# ebox.net
KiCad netlist of a schematic drawn in EAGLE
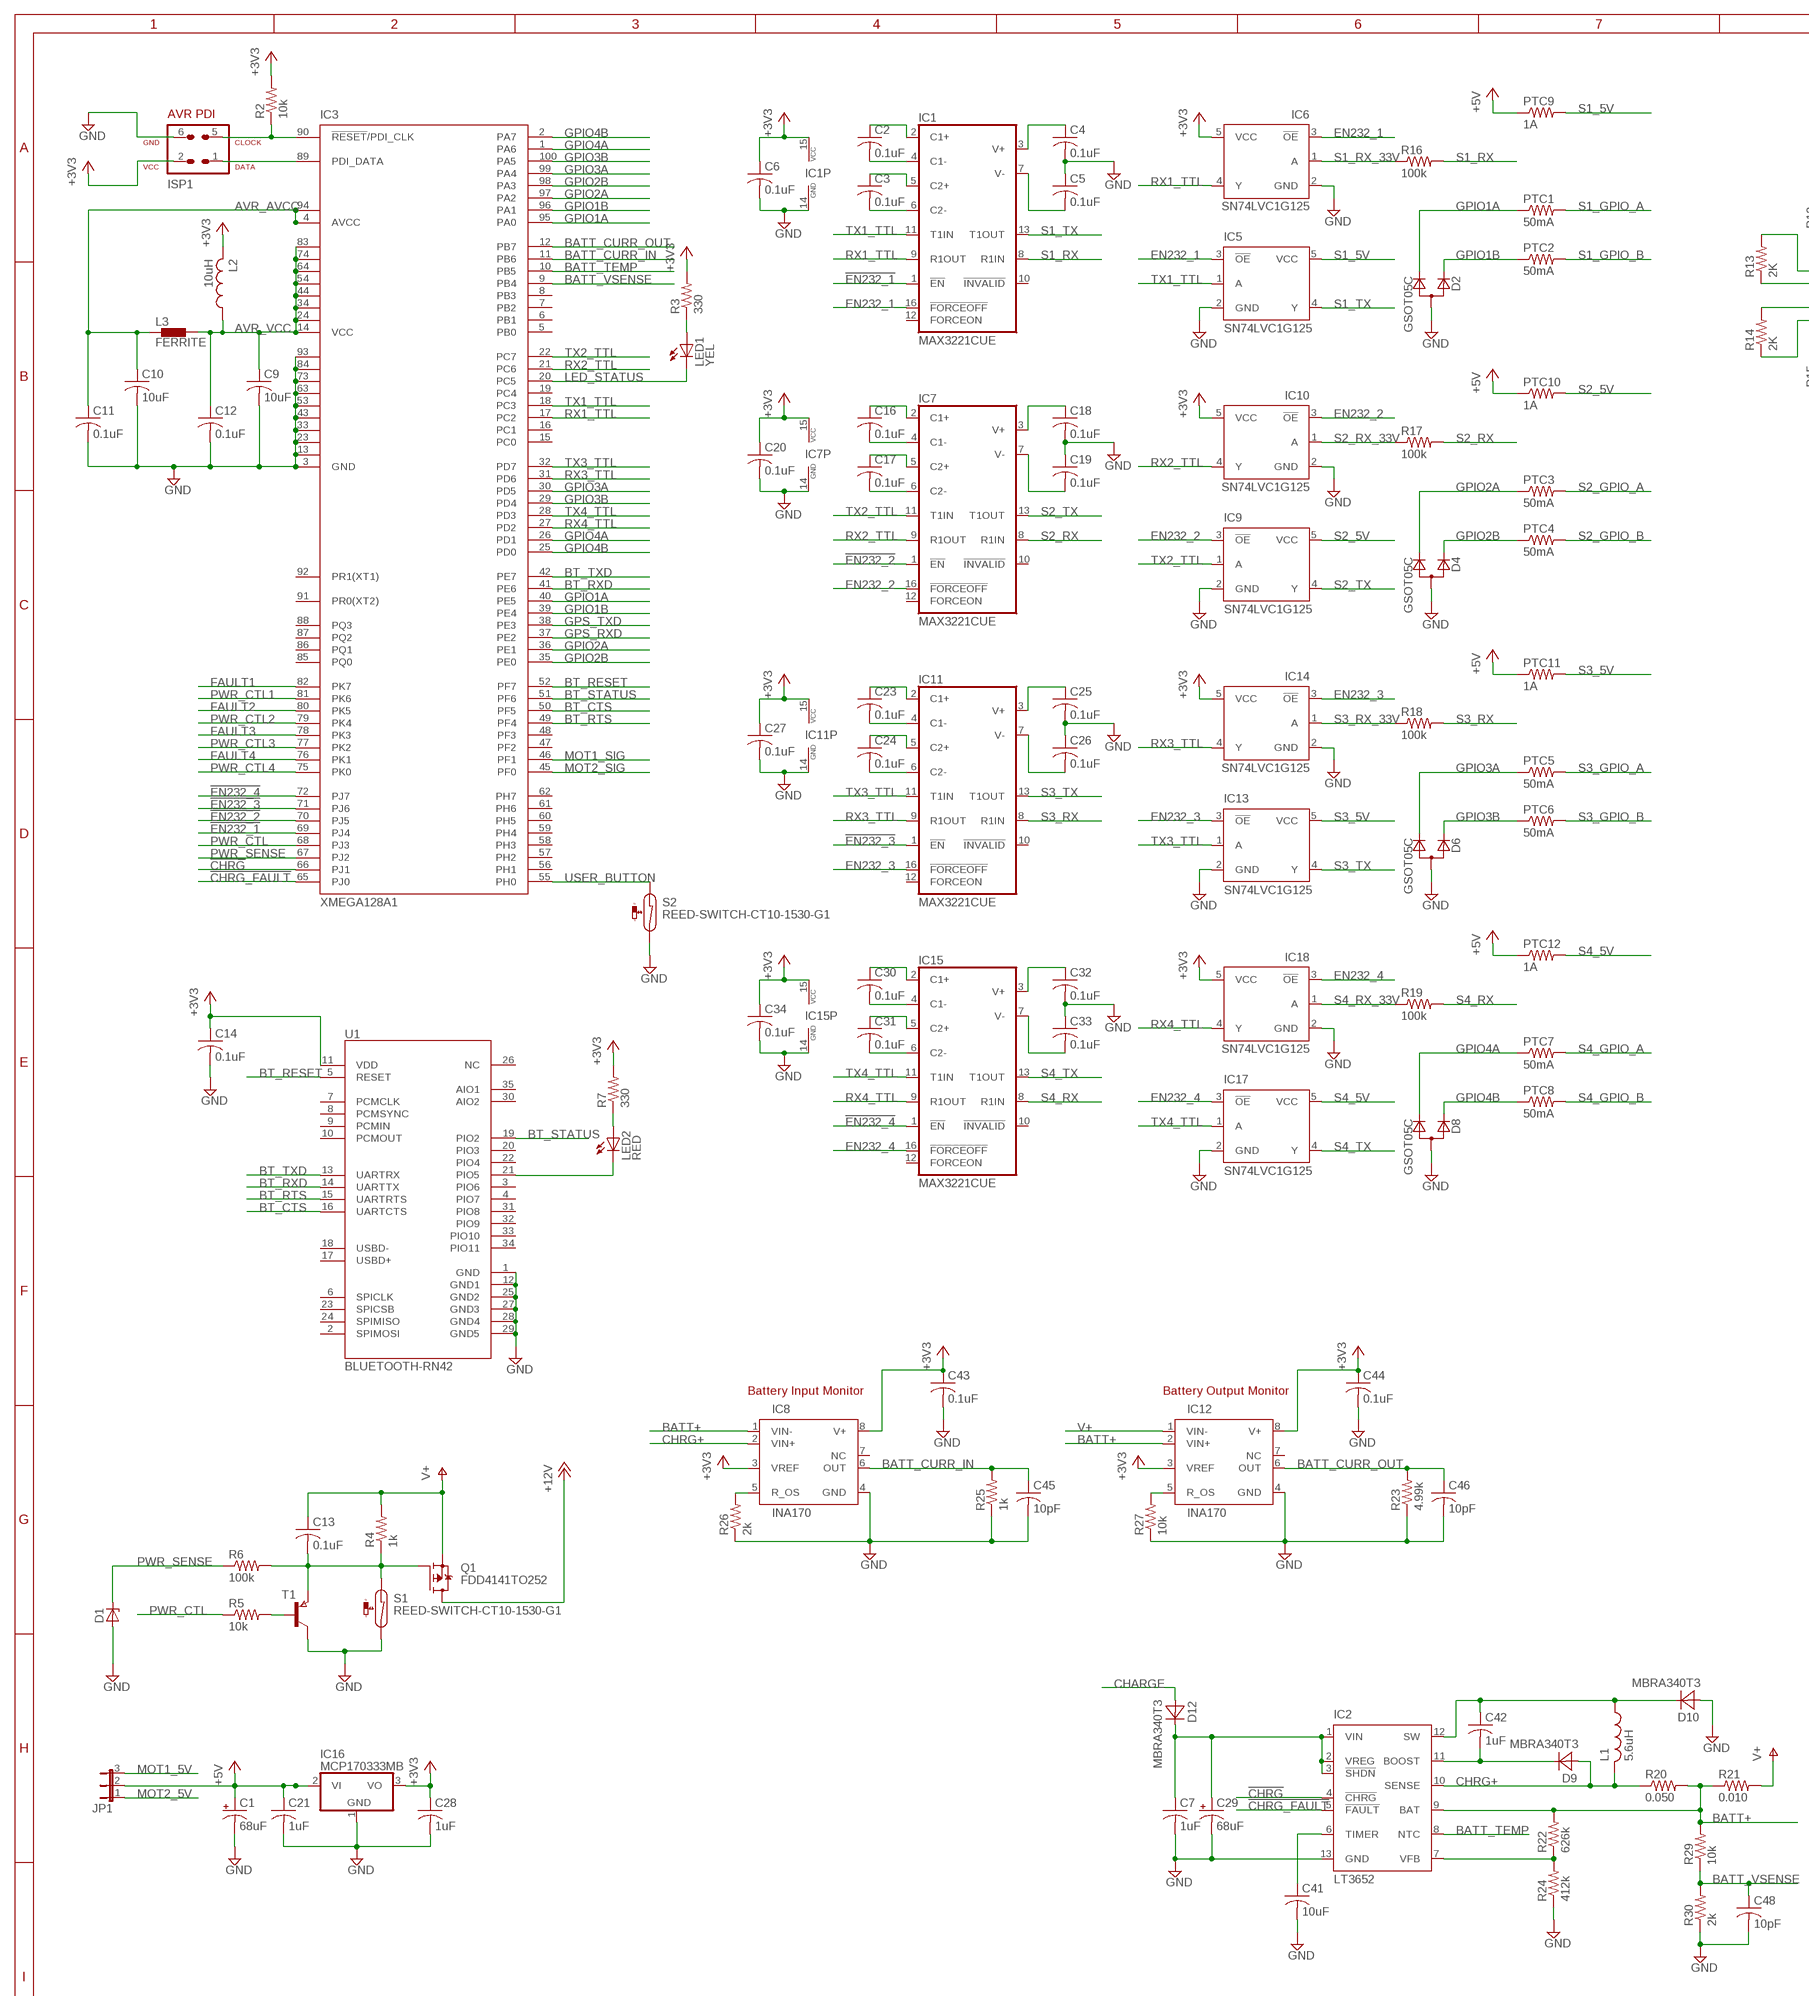
[diagram p0: schematic, sheet 1, part 1 of 2]
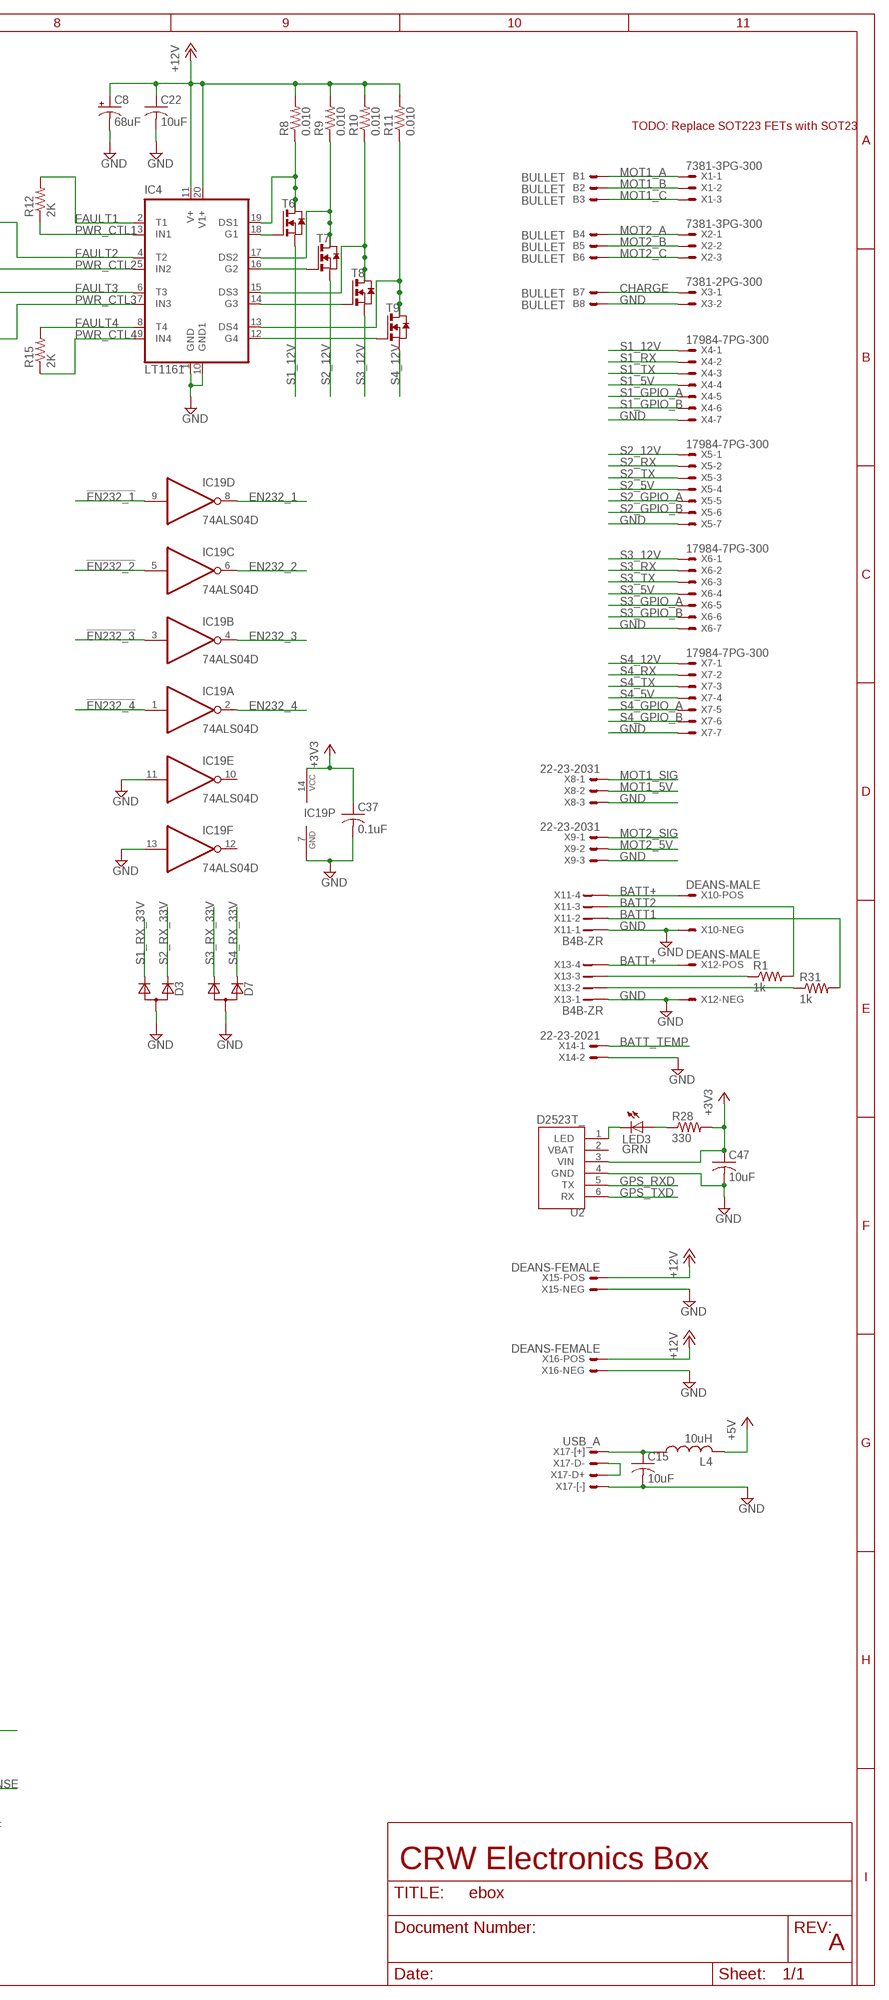
[diagram p1: schematic, sheet 1, part 2 of 2]

(export (version "E")
  (design (tool "Eeschema 10.0.6"))
  (components
    (comp (ref "B1")
      (value "BULLET")
      (footprint "eagle-import:BULLET")
      (libsource (lib "eagle-import") (part "BULLET"))
    )
    (comp (ref "B2")
      (value "BULLET")
      (footprint "eagle-import:BULLET")
      (libsource (lib "eagle-import") (part "BULLET"))
    )
    (comp (ref "B3")
      (value "BULLET")
      (footprint "eagle-import:BULLET")
      (libsource (lib "eagle-import") (part "BULLET"))
    )
    (comp (ref "B4")
      (value "BULLET")
      (footprint "eagle-import:BULLET")
      (libsource (lib "eagle-import") (part "BULLET"))
    )
    (comp (ref "B5")
      (value "BULLET")
      (footprint "eagle-import:BULLET")
      (libsource (lib "eagle-import") (part "BULLET"))
    )
    (comp (ref "B6")
      (value "BULLET")
      (footprint "eagle-import:BULLET")
      (libsource (lib "eagle-import") (part "BULLET"))
    )
    (comp (ref "B7")
      (value "BULLET")
      (footprint "eagle-import:BULLET")
      (libsource (lib "eagle-import") (part "BULLET"))
    )
    (comp (ref "B8")
      (value "BULLET")
      (footprint "eagle-import:BULLET")
      (libsource (lib "eagle-import") (part "BULLET"))
    )
    (comp (ref "C1")
      (value "68uF")
      (footprint "eagle-import:PANASONIC_D")
      (libsource (lib "eagle-import") (part "CPOL-USD"))
    )
    (comp (ref "C2")
      (value "0.1uF")
      (footprint "eagle-import:C0805")
      (libsource (lib "eagle-import") (part "C-USC0805"))
    )
    (comp (ref "C3")
      (value "0.1uF")
      (footprint "eagle-import:C0805")
      (libsource (lib "eagle-import") (part "C-USC0805"))
    )
    (comp (ref "C4")
      (value "0.1uF")
      (footprint "eagle-import:C0805")
      (libsource (lib "eagle-import") (part "C-USC0805"))
    )
    (comp (ref "C5")
      (value "0.1uF")
      (footprint "eagle-import:C0805")
      (libsource (lib "eagle-import") (part "C-USC0805"))
    )
    (comp (ref "C6")
      (value "0.1uF")
      (footprint "eagle-import:C0805")
      (libsource (lib "eagle-import") (part "C-USC0805"))
    )
    (comp (ref "C7")
      (value "1uF")
      (footprint "eagle-import:C0805")
      (libsource (lib "eagle-import") (part "C-USC0805"))
    )
    (comp (ref "C8")
      (value "68uF")
      (footprint "eagle-import:PANASONIC_D")
      (libsource (lib "eagle-import") (part "CPOL-USD"))
    )
    (comp (ref "C9")
      (value "10uF")
      (footprint "eagle-import:C0805")
      (libsource (lib "eagle-import") (part "C-USC0805"))
    )
    (comp (ref "C10")
      (value "10uF")
      (footprint "eagle-import:C0805")
      (libsource (lib "eagle-import") (part "C-USC0805"))
    )
    (comp (ref "C11")
      (value "0.1uF")
      (footprint "eagle-import:C0805")
      (libsource (lib "eagle-import") (part "C-USC0805"))
    )
    (comp (ref "C12")
      (value "0.1uF")
      (footprint "eagle-import:C0805")
      (libsource (lib "eagle-import") (part "C-USC0805"))
    )
    (comp (ref "C13")
      (value "0.1uF")
      (footprint "eagle-import:C0805")
      (libsource (lib "eagle-import") (part "C-USC0805"))
    )
    (comp (ref "C14")
      (value "0.1uF")
      (footprint "eagle-import:C0805")
      (libsource (lib "eagle-import") (part "C-USC0805"))
    )
    (comp (ref "C15")
      (value "10uF")
      (footprint "eagle-import:C0805")
      (libsource (lib "eagle-import") (part "C-USC0805"))
    )
    (comp (ref "C16")
      (value "0.1uF")
      (footprint "eagle-import:C0805")
      (libsource (lib "eagle-import") (part "C-USC0805"))
    )
    (comp (ref "C17")
      (value "0.1uF")
      (footprint "eagle-import:C0805")
      (libsource (lib "eagle-import") (part "C-USC0805"))
    )
    (comp (ref "C18")
      (value "0.1uF")
      (footprint "eagle-import:C0805")
      (libsource (lib "eagle-import") (part "C-USC0805"))
    )
    (comp (ref "C19")
      (value "0.1uF")
      (footprint "eagle-import:C0805")
      (libsource (lib "eagle-import") (part "C-USC0805"))
    )
    (comp (ref "C20")
      (value "0.1uF")
      (footprint "eagle-import:C0805")
      (libsource (lib "eagle-import") (part "C-USC0805"))
    )
    (comp (ref "C21")
      (value "1uF")
      (footprint "eagle-import:C0805")
      (libsource (lib "eagle-import") (part "C-USC0805"))
    )
    (comp (ref "C22")
      (value "10uF")
      (footprint "eagle-import:C0805")
      (libsource (lib "eagle-import") (part "C-USC0805"))
    )
    (comp (ref "C23")
      (value "0.1uF")
      (footprint "eagle-import:C0805")
      (libsource (lib "eagle-import") (part "C-USC0805"))
    )
    (comp (ref "C24")
      (value "0.1uF")
      (footprint "eagle-import:C0805")
      (libsource (lib "eagle-import") (part "C-USC0805"))
    )
    (comp (ref "C25")
      (value "0.1uF")
      (footprint "eagle-import:C0805")
      (libsource (lib "eagle-import") (part "C-USC0805"))
    )
    (comp (ref "C26")
      (value "0.1uF")
      (footprint "eagle-import:C0805")
      (libsource (lib "eagle-import") (part "C-USC0805"))
    )
    (comp (ref "C27")
      (value "0.1uF")
      (footprint "eagle-import:C0805")
      (libsource (lib "eagle-import") (part "C-USC0805"))
    )
    (comp (ref "C28")
      (value "1uF")
      (footprint "eagle-import:C0805")
      (libsource (lib "eagle-import") (part "C-USC0805"))
    )
    (comp (ref "C29")
      (value "68uF")
      (footprint "eagle-import:PANASONIC_D")
      (libsource (lib "eagle-import") (part "CPOL-USD"))
    )
    (comp (ref "C30")
      (value "0.1uF")
      (footprint "eagle-import:C0805")
      (libsource (lib "eagle-import") (part "C-USC0805"))
    )
    (comp (ref "C31")
      (value "0.1uF")
      (footprint "eagle-import:C0805")
      (libsource (lib "eagle-import") (part "C-USC0805"))
    )
    (comp (ref "C32")
      (value "0.1uF")
      (footprint "eagle-import:C0805")
      (libsource (lib "eagle-import") (part "C-USC0805"))
    )
    (comp (ref "C33")
      (value "0.1uF")
      (footprint "eagle-import:C0805")
      (libsource (lib "eagle-import") (part "C-USC0805"))
    )
    (comp (ref "C34")
      (value "0.1uF")
      (footprint "eagle-import:C0805")
      (libsource (lib "eagle-import") (part "C-USC0805"))
    )
    (comp (ref "C37")
      (value "0.1uF")
      (footprint "eagle-import:C0805")
      (libsource (lib "eagle-import") (part "C-USC0805"))
    )
    (comp (ref "C41")
      (value "10uF")
      (footprint "eagle-import:C0805")
      (libsource (lib "eagle-import") (part "C-USC0805"))
    )
    (comp (ref "C42")
      (value "1uF")
      (footprint "eagle-import:C0805")
      (libsource (lib "eagle-import") (part "C-USC0805"))
    )
    (comp (ref "C43")
      (value "0.1uF")
      (footprint "eagle-import:C0805")
      (libsource (lib "eagle-import") (part "C-USC0805"))
    )
    (comp (ref "C44")
      (value "0.1uF")
      (footprint "eagle-import:C0805")
      (libsource (lib "eagle-import") (part "C-USC0805"))
    )
    (comp (ref "C45")
      (value "10pF")
      (footprint "eagle-import:C0805")
      (libsource (lib "eagle-import") (part "C-USC0805"))
    )
    (comp (ref "C46")
      (value "10pF")
      (footprint "eagle-import:C0805")
      (libsource (lib "eagle-import") (part "C-USC0805"))
    )
    (comp (ref "C47")
      (value "10uF")
      (footprint "eagle-import:C0805")
      (libsource (lib "eagle-import") (part "C-USC0805"))
    )
    (comp (ref "C48")
      (value "10pF")
      (footprint "eagle-import:C0805")
      (libsource (lib "eagle-import") (part "C-USC0805"))
    )
    (comp (ref "D1")
      (value "ZENER-DIODESOT23")
      (footprint "eagle-import:SOT23")
      (libsource (lib "eagle-import") (part "ZENER-DIODESOT23"))
    )
    (comp (ref "D2")
      (value "GSOT05C")
      (footprint "eagle-import:SOT-23")
      (libsource (lib "eagle-import") (part "D_2CSOT23"))
    )
    (comp (ref "D3")
      (value "D_2CSOT23")
      (footprint "eagle-import:SOT-23")
      (libsource (lib "eagle-import") (part "D_2CSOT23"))
    )
    (comp (ref "D4")
      (value "GSOT05C")
      (footprint "eagle-import:SOT-23")
      (libsource (lib "eagle-import") (part "D_2CSOT23"))
    )
    (comp (ref "D6")
      (value "GSOT05C")
      (footprint "eagle-import:SOT-23")
      (libsource (lib "eagle-import") (part "D_2CSOT23"))
    )
    (comp (ref "D7")
      (value "D_2CSOT23")
      (footprint "eagle-import:SOT-23")
      (libsource (lib "eagle-import") (part "D_2CSOT23"))
    )
    (comp (ref "D8")
      (value "GSOT05C")
      (footprint "eagle-import:SOT-23")
      (libsource (lib "eagle-import") (part "D_2CSOT23"))
    )
    (comp (ref "D9")
      (value "MBRA340T3")
      (footprint "eagle-import:SMA")
      (libsource (lib "eagle-import") (part "MBRA340T3"))
    )
    (comp (ref "D10")
      (value "MBRA340T3")
      (footprint "eagle-import:SMA")
      (libsource (lib "eagle-import") (part "MBRA340T3"))
    )
    (comp (ref "D12")
      (value "MBRA340T3")
      (footprint "eagle-import:SMA")
      (libsource (lib "eagle-import") (part "MBRA340T3"))
    )
    (comp (ref "IC1")
      (value "MAX3221CUE")
      (footprint "eagle-import:TSSOP16")
      (fields (field (name "MF") "MAXIM") (field (name "MPN") "MAX3221CUE+"))
      (libsource (lib "eagle-import") (part "MAX3221UEC"))
    )
    (comp (ref "IC2")
      (value "LT3652")
      (footprint "eagle-import:MSOP12-MSE")
      (fields (field (name "MPN") "AD7992BRMZ-0"))
      (libsource (lib "eagle-import") (part "LT3652"))
    )
    (comp (ref "IC3")
      (value "XMEGA128A1")
      (footprint "eagle-import:TQFP100")
      (libsource (lib "eagle-import") (part "XMEGA128A1"))
    )
    (comp (ref "IC4")
      (value "LT1161")
      (footprint "eagle-import:SOIC20R")
      (libsource (lib "eagle-import") (part "LT1161"))
    )
    (comp (ref "IC5")
      (value "SN74LVC1G125")
      (footprint "eagle-import:SOT23-DBV")
      (libsource (lib "eagle-import") (part "SN74LVC1G125"))
    )
    (comp (ref "IC6")
      (value "SN74LVC1G125")
      (footprint "eagle-import:SOT23-DBV")
      (libsource (lib "eagle-import") (part "SN74LVC1G125"))
    )
    (comp (ref "IC7")
      (value "MAX3221CUE")
      (footprint "eagle-import:TSSOP16")
      (fields (field (name "MF") "MAXIM") (field (name "MPN") "MAX3221CUE+"))
      (libsource (lib "eagle-import") (part "MAX3221UEC"))
    )
    (comp (ref "IC8")
      (value "INA170")
      (footprint "eagle-import:MSOP8")
      (libsource (lib "eagle-import") (part "INA170"))
    )
    (comp (ref "IC9")
      (value "SN74LVC1G125")
      (footprint "eagle-import:SOT23-DBV")
      (libsource (lib "eagle-import") (part "SN74LVC1G125"))
    )
    (comp (ref "IC10")
      (value "SN74LVC1G125")
      (footprint "eagle-import:SOT23-DBV")
      (libsource (lib "eagle-import") (part "SN74LVC1G125"))
    )
    (comp (ref "IC11")
      (value "MAX3221CUE")
      (footprint "eagle-import:TSSOP16")
      (fields (field (name "MF") "MAXIM") (field (name "MPN") "MAX3221CUE+"))
      (libsource (lib "eagle-import") (part "MAX3221UEC"))
    )
    (comp (ref "IC12")
      (value "INA170")
      (footprint "eagle-import:MSOP8")
      (libsource (lib "eagle-import") (part "INA170"))
    )
    (comp (ref "IC13")
      (value "SN74LVC1G125")
      (footprint "eagle-import:SOT23-DBV")
      (libsource (lib "eagle-import") (part "SN74LVC1G125"))
    )
    (comp (ref "IC14")
      (value "SN74LVC1G125")
      (footprint "eagle-import:SOT23-DBV")
      (libsource (lib "eagle-import") (part "SN74LVC1G125"))
    )
    (comp (ref "IC15")
      (value "MAX3221CUE")
      (footprint "eagle-import:TSSOP16")
      (fields (field (name "MF") "MAXIM") (field (name "MPN") "MAX3221CUE+"))
      (libsource (lib "eagle-import") (part "MAX3221UEC"))
    )
    (comp (ref "IC16")
      (value "MCP170333MB")
      (footprint "eagle-import:SOT89")
      (libsource (lib "eagle-import") (part "MCP1703MB33"))
    )
    (comp (ref "IC17")
      (value "SN74LVC1G125")
      (footprint "eagle-import:SOT23-DBV")
      (libsource (lib "eagle-import") (part "SN74LVC1G125"))
    )
    (comp (ref "IC18")
      (value "SN74LVC1G125")
      (footprint "eagle-import:SOT23-DBV")
      (libsource (lib "eagle-import") (part "SN74LVC1G125"))
    )
    (comp (ref "IC19")
      (value "74ALS04D")
      (footprint "eagle-import:SO14")
      (libsource (lib "eagle-import") (part "7404DALS"))
    )
    (comp (ref "ISP1")
      (value "AVR-PDIVERT")
      (footprint "eagle-import:AVR-ISP-6")
      (libsource (lib "eagle-import") (part "AVR-PDIVERT"))
    )
    (comp (ref "JP1")
      (value "JP2E")
      (footprint "eagle-import:JP2")
      (libsource (lib "eagle-import") (part "JP2E"))
    )
    (comp (ref "L1")
      (value "5.6uH")
      (footprint "eagle-import:IHLP-2020CZ-11")
      (libsource (lib "eagle-import") (part "IHLP-2020CZ-11"))
    )
    (comp (ref "L2")
      (value "10uH")
      (footprint "eagle-import:L2012C")
      (libsource (lib "eagle-import") (part "L-USL2012C"))
    )
    (comp (ref "L3")
      (value "FERRITE")
      (footprint "eagle-import:0402")
      (libsource (lib "eagle-import") (part "BML15HB121SN1"))
    )
    (comp (ref "L4")
      (value "10uH")
      (footprint "eagle-import:L2012C")
      (libsource (lib "eagle-import") (part "L-USL2012C"))
    )
    (comp (ref "LED1")
      (value "YEL")
      (footprint "eagle-import:CHIPLED_1206")
      (libsource (lib "eagle-import") (part "LEDCHIPLED_1206"))
    )
    (comp (ref "LED2")
      (value "RED")
      (footprint "eagle-import:CHIPLED_1206")
      (libsource (lib "eagle-import") (part "LEDCHIPLED_1206"))
    )
    (comp (ref "LED3")
      (value "GRN")
      (footprint "eagle-import:CHIPLED_1206")
      (libsource (lib "eagle-import") (part "LEDCHIPLED_1206"))
    )
    (comp (ref "PTC1")
      (value "50mA")
      (footprint "eagle-import:R1206")
      (libsource (lib "eagle-import") (part "R-US_R1206"))
    )
    (comp (ref "PTC2")
      (value "50mA")
      (footprint "eagle-import:R1206")
      (libsource (lib "eagle-import") (part "R-US_R1206"))
    )
    (comp (ref "PTC3")
      (value "50mA")
      (footprint "eagle-import:R1206")
      (libsource (lib "eagle-import") (part "R-US_R1206"))
    )
    (comp (ref "PTC4")
      (value "50mA")
      (footprint "eagle-import:R1206")
      (libsource (lib "eagle-import") (part "R-US_R1206"))
    )
    (comp (ref "PTC5")
      (value "50mA")
      (footprint "eagle-import:R1206")
      (libsource (lib "eagle-import") (part "R-US_R1206"))
    )
    (comp (ref "PTC6")
      (value "50mA")
      (footprint "eagle-import:R1206")
      (libsource (lib "eagle-import") (part "R-US_R1206"))
    )
    (comp (ref "PTC7")
      (value "50mA")
      (footprint "eagle-import:R1206")
      (libsource (lib "eagle-import") (part "R-US_R1206"))
    )
    (comp (ref "PTC8")
      (value "50mA")
      (footprint "eagle-import:R1206")
      (libsource (lib "eagle-import") (part "R-US_R1206"))
    )
    (comp (ref "PTC9")
      (value "1A")
      (footprint "eagle-import:R1206")
      (libsource (lib "eagle-import") (part "R-US_R1206"))
    )
    (comp (ref "PTC10")
      (value "1A")
      (footprint "eagle-import:R1206")
      (libsource (lib "eagle-import") (part "R-US_R1206"))
    )
    (comp (ref "PTC11")
      (value "1A")
      (footprint "eagle-import:R1206")
      (libsource (lib "eagle-import") (part "R-US_R1206"))
    )
    (comp (ref "PTC12")
      (value "1A")
      (footprint "eagle-import:R1206")
      (libsource (lib "eagle-import") (part "R-US_R1206"))
    )
    (comp (ref "Q1")
      (value "FDD4141TO252")
      (footprint "eagle-import:TO252")
      (libsource (lib "eagle-import") (part "FDD4141TO252"))
    )
    (comp (ref "R1")
      (value "1k")
      (footprint "eagle-import:R0805")
      (libsource (lib "eagle-import") (part "R-US_R0805"))
    )
    (comp (ref "R2")
      (value "10k")
      (footprint "eagle-import:R0805")
      (libsource (lib "eagle-import") (part "R-US_R0805"))
    )
    (comp (ref "R3")
      (value "330")
      (footprint "eagle-import:R0805")
      (libsource (lib "eagle-import") (part "R-US_R0805"))
    )
    (comp (ref "R4")
      (value "1k")
      (footprint "eagle-import:R0805")
      (libsource (lib "eagle-import") (part "R-US_R0805"))
    )
    (comp (ref "R5")
      (value "10k")
      (footprint "eagle-import:R0805")
      (libsource (lib "eagle-import") (part "R-US_R0805"))
    )
    (comp (ref "R6")
      (value "100k")
      (footprint "eagle-import:R0805")
      (libsource (lib "eagle-import") (part "R-US_R0805"))
    )
    (comp (ref "R7")
      (value "330")
      (footprint "eagle-import:R0805")
      (libsource (lib "eagle-import") (part "R-US_R0805"))
    )
    (comp (ref "R8")
      (value "0.010")
      (footprint "eagle-import:R6332")
      (libsource (lib "eagle-import") (part "R-US_R6332"))
    )
    (comp (ref "R9")
      (value "0.010")
      (footprint "eagle-import:R6332")
      (libsource (lib "eagle-import") (part "R-US_R6332"))
    )
    (comp (ref "R10")
      (value "0.010")
      (footprint "eagle-import:R6332")
      (libsource (lib "eagle-import") (part "R-US_R6332"))
    )
    (comp (ref "R11")
      (value "0.010")
      (footprint "eagle-import:R6332")
      (libsource (lib "eagle-import") (part "R-US_R6332"))
    )
    (comp (ref "R12")
      (value "2K")
      (footprint "eagle-import:R0805")
      (libsource (lib "eagle-import") (part "R-US_R0805"))
    )
    (comp (ref "R13")
      (value "2K")
      (footprint "eagle-import:R0805")
      (libsource (lib "eagle-import") (part "R-US_R0805"))
    )
    (comp (ref "R14")
      (value "2K")
      (footprint "eagle-import:R0805")
      (libsource (lib "eagle-import") (part "R-US_R0805"))
    )
    (comp (ref "R15")
      (value "2K")
      (footprint "eagle-import:R0805")
      (libsource (lib "eagle-import") (part "R-US_R0805"))
    )
    (comp (ref "R16")
      (value "100k")
      (footprint "eagle-import:R0805")
      (libsource (lib "eagle-import") (part "R-US_R0805"))
    )
    (comp (ref "R17")
      (value "100k")
      (footprint "eagle-import:R0805")
      (libsource (lib "eagle-import") (part "R-US_R0805"))
    )
    (comp (ref "R18")
      (value "100k")
      (footprint "eagle-import:R0805")
      (libsource (lib "eagle-import") (part "R-US_R0805"))
    )
    (comp (ref "R19")
      (value "100k")
      (footprint "eagle-import:R0805")
      (libsource (lib "eagle-import") (part "R-US_R0805"))
    )
    (comp (ref "R20")
      (value "0.050")
      (footprint "eagle-import:R6332")
      (libsource (lib "eagle-import") (part "R-US_R6332"))
    )
    (comp (ref "R21")
      (value "0.010")
      (footprint "eagle-import:R6332")
      (libsource (lib "eagle-import") (part "R-US_R6332"))
    )
    (comp (ref "R22")
      (value "626k")
      (footprint "eagle-import:R0805")
      (libsource (lib "eagle-import") (part "R-US_R0805"))
    )
    (comp (ref "R23")
      (value "4.99k")
      (footprint "eagle-import:R0805")
      (libsource (lib "eagle-import") (part "R-US_R0805"))
    )
    (comp (ref "R24")
      (value "412k")
      (footprint "eagle-import:R0805")
      (libsource (lib "eagle-import") (part "R-US_R0805"))
    )
    (comp (ref "R25")
      (value "1k")
      (footprint "eagle-import:R0805")
      (libsource (lib "eagle-import") (part "R-US_R0805"))
    )
    (comp (ref "R26")
      (value "2k")
      (footprint "eagle-import:R0805")
      (libsource (lib "eagle-import") (part "R-US_R0805"))
    )
    (comp (ref "R27")
      (value "10k")
      (footprint "eagle-import:R0805")
      (libsource (lib "eagle-import") (part "R-US_R0805"))
    )
    (comp (ref "R28")
      (value "330")
      (footprint "eagle-import:R0805")
      (libsource (lib "eagle-import") (part "R-US_R0805"))
    )
    (comp (ref "R29")
      (value "10k")
      (footprint "eagle-import:R0805")
      (libsource (lib "eagle-import") (part "R-US_R0805"))
    )
    (comp (ref "R30")
      (value "2k")
      (footprint "eagle-import:R0805")
      (libsource (lib "eagle-import") (part "R-US_R0805"))
    )
    (comp (ref "R31")
      (value "1k")
      (footprint "eagle-import:R0805")
      (libsource (lib "eagle-import") (part "R-US_R0805"))
    )
    (comp (ref "S1")
      (value "REED-SWITCH-CT10-1530-G1")
      (footprint "eagle-import:CT10-G1")
      (fields (field (name "MF") "COTO TECHNOLOGY") (field (name "MPN") "CT10-1530-G1"))
      (libsource (lib "eagle-import") (part "REED-SWITCH-CT10-1530-G1"))
    )
    (comp (ref "S2")
      (value "REED-SWITCH-CT10-1530-G1")
      (footprint "eagle-import:CT10-G1")
      (fields (field (name "MF") "COTO TECHNOLOGY") (field (name "MPN") "CT10-1530-G1"))
      (libsource (lib "eagle-import") (part "REED-SWITCH-CT10-1530-G1"))
    )
    (comp (ref "T1")
      (value "PNPSOT23")
      (footprint "eagle-import:SOT-23")
      (fields (field (name "MPN") "DSS20200L-7"))
      (libsource (lib "eagle-import") (part "PNPSOT23"))
    )
    (comp (ref "T6")
      (value "NMOSSOT23-6")
      (footprint "eagle-import:SOT23-6")
      (libsource (lib "eagle-import") (part "NMOSSOT23-6"))
    )
    (comp (ref "T7")
      (value "NMOSSOT23-6")
      (footprint "eagle-import:SOT23-6")
      (libsource (lib "eagle-import") (part "NMOSSOT23-6"))
    )
    (comp (ref "T8")
      (value "NMOSSOT23-6")
      (footprint "eagle-import:SOT23-6")
      (libsource (lib "eagle-import") (part "NMOSSOT23-6"))
    )
    (comp (ref "T9")
      (value "NMOSSOT23-6")
      (footprint "eagle-import:SOT23-6")
      (libsource (lib "eagle-import") (part "NMOSSOT23-6"))
    )
    (comp (ref "U1")
      (value "BLUETOOTH-RN42")
      (footprint "eagle-import:RN41")
      (libsource (lib "eagle-import") (part "BLUETOOTH-RN41{dblquote}"))
    )
    (comp (ref "U2")
      (value "D2523T_")
      (footprint "eagle-import:EM406")
      (libsource (lib "eagle-import") (part "D2523T_"))
    )
    (comp (ref "X1")
      (value "7381-3PG-300")
      (footprint "eagle-import:7381-3PG-300")
      (libsource (lib "eagle-import") (part "7381-3PG-300"))
    )
    (comp (ref "X2")
      (value "7381-3PG-300")
      (footprint "eagle-import:7381-3PG-300")
      (libsource (lib "eagle-import") (part "7381-3PG-300"))
    )
    (comp (ref "X3")
      (value "7381-2PG-300")
      (footprint "eagle-import:7381-2PG-300")
      (libsource (lib "eagle-import") (part "7381-2PG-300"))
    )
    (comp (ref "X4")
      (value "17984-7PG-300")
      (footprint "eagle-import:17984-7PG-300")
      (libsource (lib "eagle-import") (part "17984-7PG-300"))
    )
    (comp (ref "X5")
      (value "17984-7PG-300")
      (footprint "eagle-import:17984-7PG-300")
      (libsource (lib "eagle-import") (part "17984-7PG-300"))
    )
    (comp (ref "X6")
      (value "17984-7PG-300")
      (footprint "eagle-import:17984-7PG-300")
      (libsource (lib "eagle-import") (part "17984-7PG-300"))
    )
    (comp (ref "X7")
      (value "17984-7PG-300")
      (footprint "eagle-import:17984-7PG-300")
      (libsource (lib "eagle-import") (part "17984-7PG-300"))
    )
    (comp (ref "X8")
      (value "22-23-2031")
      (footprint "eagle-import:22-23-2031")
      (fields (field (name "MF") "MOLEX"))
      (libsource (lib "eagle-import") (part "22-23-2031"))
    )
    (comp (ref "X9")
      (value "22-23-2031")
      (footprint "eagle-import:22-23-2031")
      (fields (field (name "MF") "MOLEX"))
      (libsource (lib "eagle-import") (part "22-23-2031"))
    )
    (comp (ref "X10")
      (value "DEANS-MALE")
      (footprint "eagle-import:DEANS_MALE")
      (libsource (lib "eagle-import") (part "DEANS-MALE"))
    )
    (comp (ref "X11")
      (value "B4B-ZR")
      (footprint "eagle-import:B4B-ZR")
      (fields (field (name "MF") "FARNELL") (field (name "MPN") "B4B-ZR(LF)(SN)"))
      (libsource (lib "eagle-import") (part "?4B-ZRB"))
    )
    (comp (ref "X12")
      (value "DEANS-MALE")
      (footprint "eagle-import:DEANS_MALE")
      (libsource (lib "eagle-import") (part "DEANS-MALE"))
    )
    (comp (ref "X13")
      (value "B4B-ZR")
      (footprint "eagle-import:B4B-ZR")
      (fields (field (name "MF") "FARNELL") (field (name "MPN") "B4B-ZR(LF)(SN)"))
      (libsource (lib "eagle-import") (part "?4B-ZRB"))
    )
    (comp (ref "X14")
      (value "22-23-2021")
      (footprint "eagle-import:22-23-2021")
      (fields (field (name "MF") "MOLEX"))
      (libsource (lib "eagle-import") (part "22-23-2021"))
    )
    (comp (ref "X15")
      (value "DEANS-FEMALE")
      (footprint "eagle-import:DEANS_FEMALE")
      (libsource (lib "eagle-import") (part "DEANS-FEMALE"))
    )
    (comp (ref "X16")
      (value "DEANS-FEMALE")
      (footprint "eagle-import:DEANS_FEMALE")
      (libsource (lib "eagle-import") (part "DEANS-FEMALE"))
    )
    (comp (ref "X17")
      (value "USB_A")
      (footprint "eagle-import:1001-002-01100")
      (libsource (lib "eagle-import") (part "USB_A"))
    )
  )
  (nets
    (net (code "1") (name "+3V3") (class "Default")
      (node (ref "C14") (pin "1") (pinfunction "1_1") (pintype "passive"))
      (node (ref "C20") (pin "1") (pinfunction "1_1") (pintype "passive"))
      (node (ref "C27") (pin "1") (pinfunction "1_1") (pintype "passive"))
      (node (ref "C28") (pin "1") (pinfunction "1_1") (pintype "passive"))
      (node (ref "C34") (pin "1") (pinfunction "1_1") (pintype "passive"))
      (node (ref "C37") (pin "1") (pinfunction "1_1") (pintype "passive"))
      (node (ref "C43") (pin "1") (pinfunction "1_1") (pintype "passive"))
      (node (ref "C44") (pin "1") (pinfunction "1_1") (pintype "passive"))
      (node (ref "C47") (pin "1") (pinfunction "1_1") (pintype "passive"))
      (node (ref "C6") (pin "1") (pinfunction "1_1") (pintype "passive"))
      (node (ref "IC1") (pin "15") (pinfunction "VCC_15") (pintype "power_in"))
      (node (ref "IC10") (pin "5") (pinfunction "VCC_5") (pintype "passive"))
      (node (ref "IC11") (pin "15") (pinfunction "VCC_15") (pintype "power_in"))
      (node (ref "IC12") (pin "3") (pinfunction "VREF_3") (pintype "input"))
      (node (ref "IC12") (pin "8") (pinfunction "V+_8") (pintype "input"))
      (node (ref "IC14") (pin "5") (pinfunction "VCC_5") (pintype "passive"))
      (node (ref "IC15") (pin "15") (pinfunction "VCC_15") (pintype "power_in"))
      (node (ref "IC16") (pin "3") (pinfunction "VO_3") (pintype "passive"))
      (node (ref "IC18") (pin "5") (pinfunction "VCC_5") (pintype "passive"))
      (node (ref "IC19") (pin "14") (pinfunction "VCC_14") (pintype "power_in"))
      (node (ref "IC6") (pin "5") (pinfunction "VCC_5") (pintype "passive"))
      (node (ref "IC7") (pin "15") (pinfunction "VCC_15") (pintype "power_in"))
      (node (ref "IC8") (pin "3") (pinfunction "VREF_3") (pintype "input"))
      (node (ref "IC8") (pin "8") (pinfunction "V+_8") (pintype "input"))
      (node (ref "ISP1") (pin "2") (pinfunction "2_2") (pintype "passive"))
      (node (ref "L2") (pin "2") (pinfunction "2_2") (pintype "passive"))
      (node (ref "R2") (pin "2") (pinfunction "2_2") (pintype "passive"))
      (node (ref "R28") (pin "2") (pinfunction "2_2") (pintype "passive"))
      (node (ref "R3") (pin "2") (pinfunction "2_2") (pintype "passive"))
      (node (ref "R7") (pin "2") (pinfunction "2_2") (pintype "passive"))
      (node (ref "U1") (pin "11") (pinfunction "VDD_11") (pintype "bidirectional"))
      (node (ref "U2") (pin "3") (pinfunction "VIN_3") (pintype "bidirectional"))
    )
    (net (code "2") (name "+5V") (class "Default")
      (node (ref "C1") (pin "+") (pinfunction "+_+") (pintype "passive"))
      (node (ref "C21") (pin "1") (pinfunction "1_1") (pintype "passive"))
      (node (ref "IC16") (pin "2") (pinfunction "VI_2") (pintype "input"))
      (node (ref "IC16") (pin "2@1") (pinfunction "VI1_2@1") (pintype "input"))
      (node (ref "JP1") (pin "2") (pinfunction "2_2") (pintype "passive"))
      (node (ref "L4") (pin "2") (pinfunction "2_2") (pintype "passive"))
      (node (ref "PTC10") (pin "1") (pinfunction "1_1") (pintype "passive"))
      (node (ref "PTC11") (pin "1") (pinfunction "1_1") (pintype "passive"))
      (node (ref "PTC12") (pin "1") (pinfunction "1_1") (pintype "passive"))
      (node (ref "PTC9") (pin "1") (pinfunction "1_1") (pintype "passive"))
    )
    (net (code "3") (name "+12V") (class "Default")
      (node (ref "C22") (pin "1") (pinfunction "1_1") (pintype "passive"))
      (node (ref "C8") (pin "+") (pinfunction "+_+") (pintype "passive"))
      (node (ref "IC4") (pin "11") (pinfunction "V+_11") (pintype "input"))
      (node (ref "IC4") (pin "20") (pinfunction "V1+_20") (pintype "input"))
      (node (ref "Q1") (pin "3") (pinfunction "D_3") (pintype "passive"))
      (node (ref "R10") (pin "2") (pinfunction "2_2") (pintype "passive"))
      (node (ref "R11") (pin "2") (pinfunction "2_2") (pintype "passive"))
      (node (ref "R8") (pin "2") (pinfunction "2_2") (pintype "passive"))
      (node (ref "R9") (pin "2") (pinfunction "2_2") (pintype "passive"))
      (node (ref "X15") (pin "POS") (pinfunction "S_POS") (pintype "passive"))
      (node (ref "X16") (pin "POS") (pinfunction "S_POS") (pintype "passive"))
    )
    (net (code "4") (name "/AVR_AVCC") (class "Default")
      (node (ref "C10") (pin "1") (pinfunction "1_1") (pintype "passive"))
      (node (ref "C11") (pin "1") (pinfunction "1_1") (pintype "passive"))
      (node (ref "IC3") (pin "4") (pinfunction "AVCC_4") (pintype "power_in"))
      (node (ref "IC3") (pin "94") (pinfunction "AVCC1_94") (pintype "power_in"))
      (node (ref "L3") (pin "1") (pinfunction "1_1") (pintype "passive"))
    )
    (net (code "5") (name "/AVR_VCC") (class "Default")
      (node (ref "C12") (pin "1") (pinfunction "1_1") (pintype "passive"))
      (node (ref "C9") (pin "1") (pinfunction "1_1") (pintype "passive"))
      (node (ref "IC3") (pin "14") (pinfunction "VCC_14") (pintype "power_in"))
      (node (ref "IC3") (pin "24") (pinfunction "VCC1_24") (pintype "power_in"))
      (node (ref "IC3") (pin "34") (pinfunction "VCC2_34") (pintype "power_in"))
      (node (ref "IC3") (pin "44") (pinfunction "VCC3_44") (pintype "power_in"))
      (node (ref "IC3") (pin "54") (pinfunction "VCC4_54") (pintype "power_in"))
      (node (ref "IC3") (pin "64") (pinfunction "VCC5_64") (pintype "power_in"))
      (node (ref "IC3") (pin "74") (pinfunction "VCC6_74") (pintype "power_in"))
      (node (ref "IC3") (pin "83") (pinfunction "VCC7_83") (pintype "power_in"))
      (node (ref "L2") (pin "1") (pinfunction "1_1") (pintype "passive"))
      (node (ref "L3") (pin "2") (pinfunction "2_2") (pintype "passive"))
    )
    (net (code "6") (name "/BATT+") (class "Default")
      (node (ref "IC12") (pin "2") (pinfunction "VIN+_2") (pintype "passive"))
      (node (ref "IC2") (pin "9") (pinfunction "BAT_9") (pintype "input"))
      (node (ref "IC8") (pin "1") (pinfunction "VIN-_1") (pintype "passive"))
      (node (ref "R20") (pin "2") (pinfunction "2_2") (pintype "passive"))
      (node (ref "R21") (pin "1") (pinfunction "1_1") (pintype "passive"))
      (node (ref "R22") (pin "2") (pinfunction "2_2") (pintype "passive"))
      (node (ref "R29") (pin "2") (pinfunction "2_2") (pintype "passive"))
      (node (ref "X10") (pin "POS") (pinfunction "S_POS") (pintype "passive"))
      (node (ref "X11") (pin "4") (pinfunction "1_4") (pintype "passive"))
      (node (ref "X12") (pin "POS") (pinfunction "S_POS") (pintype "passive"))
      (node (ref "X13") (pin "4") (pinfunction "1_4") (pintype "passive"))
    )
    (net (code "7") (name "/BATT1") (class "Default")
      (node (ref "R31") (pin "2") (pinfunction "2_2") (pintype "passive"))
      (node (ref "X11") (pin "2") (pinfunction "1_2") (pintype "passive"))
    )
    (net (code "8") (name "/BATT2") (class "Default")
      (node (ref "R1") (pin "2") (pinfunction "2_2") (pintype "passive"))
      (node (ref "X11") (pin "3") (pinfunction "1_3") (pintype "passive"))
    )
    (net (code "9") (name "/BATT_CURR_IN") (class "Default")
      (node (ref "C45") (pin "1") (pinfunction "1_1") (pintype "passive"))
      (node (ref "IC3") (pin "11") (pinfunction "PB6_11") (pintype "bidirectional"))
      (node (ref "IC8") (pin "6") (pinfunction "OUT_6") (pintype "passive"))
      (node (ref "R25") (pin "2") (pinfunction "2_2") (pintype "passive"))
    )
    (net (code "10") (name "/BATT_CURR_OUT") (class "Default")
      (node (ref "C46") (pin "1") (pinfunction "1_1") (pintype "passive"))
      (node (ref "IC12") (pin "6") (pinfunction "OUT_6") (pintype "passive"))
      (node (ref "IC3") (pin "12") (pinfunction "PB7_12") (pintype "bidirectional"))
      (node (ref "R23") (pin "2") (pinfunction "2_2") (pintype "passive"))
    )
    (net (code "11") (name "/BATT_TEMP") (class "Default")
      (node (ref "IC2") (pin "8") (pinfunction "NTC_8") (pintype "bidirectional"))
      (node (ref "IC3") (pin "10") (pinfunction "PB5_10") (pintype "bidirectional"))
      (node (ref "X14") (pin "1") (pinfunction "S_1") (pintype "passive"))
    )
    (net (code "12") (name "/BATT_VSENSE") (class "Default")
      (node (ref "C48") (pin "1") (pinfunction "1_1") (pintype "passive"))
      (node (ref "IC3") (pin "9") (pinfunction "PB4_9") (pintype "bidirectional"))
      (node (ref "R29") (pin "1") (pinfunction "1_1") (pintype "passive"))
      (node (ref "R30") (pin "2") (pinfunction "2_2") (pintype "passive"))
    )
    (net (code "13") (name "/BT_CTS") (class "Default")
      (node (ref "IC3") (pin "50") (pinfunction "PF5_50") (pintype "bidirectional"))
      (node (ref "U1") (pin "16") (pinfunction "UARTCTS_16") (pintype "bidirectional"))
    )
    (net (code "14") (name "/BT_RESET") (class "Default")
      (node (ref "IC3") (pin "52") (pinfunction "PF7_52") (pintype "bidirectional"))
      (node (ref "U1") (pin "5") (pinfunction "RESET_5") (pintype "bidirectional"))
    )
    (net (code "15") (name "/BT_RTS") (class "Default")
      (node (ref "IC3") (pin "49") (pinfunction "PF4_49") (pintype "bidirectional"))
      (node (ref "U1") (pin "15") (pinfunction "UARTRTS_15") (pintype "bidirectional"))
    )
    (net (code "16") (name "/BT_RXD") (class "Default")
      (node (ref "IC3") (pin "41") (pinfunction "PE6_41") (pintype "bidirectional"))
      (node (ref "U1") (pin "14") (pinfunction "UARTTX_14") (pintype "bidirectional"))
    )
    (net (code "17") (name "/BT_STATUS") (class "Default")
      (node (ref "IC3") (pin "51") (pinfunction "PF6_51") (pintype "bidirectional"))
      (node (ref "U1") (pin "19") (pinfunction "PIO2_19") (pintype "bidirectional"))
    )
    (net (code "18") (name "/BT_TXD") (class "Default")
      (node (ref "IC3") (pin "42") (pinfunction "PE7_42") (pintype "bidirectional"))
      (node (ref "U1") (pin "13") (pinfunction "UARTRX_13") (pintype "bidirectional"))
    )
    (net (code "19") (name "/CHARGE") (class "Default")
      (node (ref "B7") (pin "P$1") (pinfunction "S_P$1") (pintype "passive"))
      (node (ref "D12") (pin "A") (pinfunction "A_A") (pintype "passive"))
      (node (ref "X3") (pin "1") (pinfunction "S_1") (pintype "passive"))
    )
    (net (code "20") (name "/CHRG+") (class "Default")
      (node (ref "D9") (pin "A") (pinfunction "A_A") (pintype "passive"))
      (node (ref "IC2") (pin "10") (pinfunction "SENSE_10") (pintype "input"))
      (node (ref "IC8") (pin "2") (pinfunction "VIN+_2") (pintype "passive"))
      (node (ref "L1") (pin "2") (pinfunction "2_2") (pintype "passive"))
      (node (ref "R20") (pin "1") (pinfunction "1_1") (pintype "passive"))
    )
    (net (code "21") (name "/EN232_1") (class "Default")
      (node (ref "IC1") (pin "16") (pinfunction "~{FORCEOFF}_16") (pintype "input"))
      (node (ref "IC19") (pin "8") (pinfunction "O_8") (pintype "output"))
      (node (ref "IC5") (pin "3") (pinfunction "~{OE}_3") (pintype "input"))
      (node (ref "IC6") (pin "3") (pinfunction "~{OE}_3") (pintype "input"))
    )
    (net (code "22") (name "/EN232_2") (class "Default")
      (node (ref "IC10") (pin "3") (pinfunction "~{OE}_3") (pintype "input"))
      (node (ref "IC19") (pin "6") (pinfunction "O_6") (pintype "output"))
      (node (ref "IC7") (pin "16") (pinfunction "~{FORCEOFF}_16") (pintype "input"))
      (node (ref "IC9") (pin "3") (pinfunction "~{OE}_3") (pintype "input"))
    )
    (net (code "23") (name "/EN232_3") (class "Default")
      (node (ref "IC11") (pin "16") (pinfunction "~{FORCEOFF}_16") (pintype "input"))
      (node (ref "IC13") (pin "3") (pinfunction "~{OE}_3") (pintype "input"))
      (node (ref "IC14") (pin "3") (pinfunction "~{OE}_3") (pintype "input"))
      (node (ref "IC19") (pin "4") (pinfunction "O_4") (pintype "output"))
    )
    (net (code "24") (name "/EN232_4") (class "Default")
      (node (ref "IC15") (pin "16") (pinfunction "~{FORCEOFF}_16") (pintype "input"))
      (node (ref "IC17") (pin "3") (pinfunction "~{OE}_3") (pintype "input"))
      (node (ref "IC18") (pin "3") (pinfunction "~{OE}_3") (pintype "input"))
      (node (ref "IC19") (pin "2") (pinfunction "O_2") (pintype "output"))
    )
    (net (code "25") (name "/FAULT1") (class "Default")
      (node (ref "IC3") (pin "82") (pinfunction "PK7_82") (pintype "bidirectional"))
      (node (ref "IC4") (pin "2") (pinfunction "T1_2") (pintype "bidirectional"))
      (node (ref "R12") (pin "2") (pinfunction "2_2") (pintype "passive"))
    )
    (net (code "26") (name "/FAULT2") (class "Default")
      (node (ref "IC3") (pin "80") (pinfunction "PK5_80") (pintype "bidirectional"))
      (node (ref "IC4") (pin "4") (pinfunction "T2_4") (pintype "bidirectional"))
      (node (ref "R13") (pin "2") (pinfunction "2_2") (pintype "passive"))
    )
    (net (code "27") (name "/FAULT3") (class "Default")
      (node (ref "IC3") (pin "78") (pinfunction "PK3_78") (pintype "bidirectional"))
      (node (ref "IC4") (pin "6") (pinfunction "T3_6") (pintype "bidirectional"))
      (node (ref "R14") (pin "2") (pinfunction "2_2") (pintype "passive"))
    )
    (net (code "28") (name "/FAULT4") (class "Default")
      (node (ref "IC3") (pin "76") (pinfunction "PK1_76") (pintype "bidirectional"))
      (node (ref "IC4") (pin "8") (pinfunction "T4_8") (pintype "input"))
      (node (ref "R15") (pin "2") (pinfunction "2_2") (pintype "passive"))
    )
    (net (code "29") (name "/GPIO1A") (class "Default")
      (node (ref "D2") (pin "3") (pinfunction "C2_3") (pintype "passive"))
      (node (ref "IC3") (pin "40") (pinfunction "PE5_40") (pintype "bidirectional"))
      (node (ref "IC3") (pin "95") (pinfunction "PA0_95") (pintype "bidirectional"))
      (node (ref "PTC1") (pin "1") (pinfunction "1_1") (pintype "passive"))
    )
    (net (code "30") (name "/GPIO1B") (class "Default")
      (node (ref "D2") (pin "2") (pinfunction "C1_2") (pintype "passive"))
      (node (ref "IC3") (pin "39") (pinfunction "PE4_39") (pintype "bidirectional"))
      (node (ref "IC3") (pin "96") (pinfunction "PA1_96") (pintype "bidirectional"))
      (node (ref "PTC2") (pin "1") (pinfunction "1_1") (pintype "passive"))
    )
    (net (code "31") (name "/GPIO2A") (class "Default")
      (node (ref "D4") (pin "3") (pinfunction "C2_3") (pintype "passive"))
      (node (ref "IC3") (pin "36") (pinfunction "PE1_36") (pintype "bidirectional"))
      (node (ref "IC3") (pin "97") (pinfunction "PA2_97") (pintype "bidirectional"))
      (node (ref "PTC3") (pin "1") (pinfunction "1_1") (pintype "passive"))
    )
    (net (code "32") (name "/GPIO2B") (class "Default")
      (node (ref "D4") (pin "2") (pinfunction "C1_2") (pintype "passive"))
      (node (ref "IC3") (pin "35") (pinfunction "PE0_35") (pintype "bidirectional"))
      (node (ref "IC3") (pin "98") (pinfunction "PA3_98") (pintype "bidirectional"))
      (node (ref "PTC4") (pin "1") (pinfunction "1_1") (pintype "passive"))
    )
    (net (code "33") (name "/GPIO3A") (class "Default")
      (node (ref "D6") (pin "3") (pinfunction "C2_3") (pintype "passive"))
      (node (ref "IC3") (pin "30") (pinfunction "PD5_30") (pintype "bidirectional"))
      (node (ref "IC3") (pin "99") (pinfunction "PA4_99") (pintype "bidirectional"))
      (node (ref "PTC5") (pin "1") (pinfunction "1_1") (pintype "passive"))
    )
    (net (code "34") (name "/GPIO3B") (class "Default")
      (node (ref "D6") (pin "2") (pinfunction "C1_2") (pintype "passive"))
      (node (ref "IC3") (pin "100") (pinfunction "PA5_100") (pintype "bidirectional"))
      (node (ref "IC3") (pin "29") (pinfunction "PD4_29") (pintype "bidirectional"))
      (node (ref "PTC6") (pin "1") (pinfunction "1_1") (pintype "passive"))
    )
    (net (code "35") (name "/GPIO4A") (class "Default")
      (node (ref "D8") (pin "3") (pinfunction "C2_3") (pintype "passive"))
      (node (ref "IC3") (pin "1") (pinfunction "PA6_1") (pintype "bidirectional"))
      (node (ref "IC3") (pin "26") (pinfunction "PD1_26") (pintype "bidirectional"))
      (node (ref "PTC7") (pin "1") (pinfunction "1_1") (pintype "passive"))
    )
    (net (code "36") (name "/GPIO4B") (class "Default")
      (node (ref "D8") (pin "2") (pinfunction "C1_2") (pintype "passive"))
      (node (ref "IC3") (pin "2") (pinfunction "PA7_2") (pintype "bidirectional"))
      (node (ref "IC3") (pin "25") (pinfunction "PD0_25") (pintype "bidirectional"))
      (node (ref "PTC8") (pin "1") (pinfunction "1_1") (pintype "passive"))
    )
    (net (code "37") (name "/GPS_RXD") (class "Default")
      (node (ref "IC3") (pin "37") (pinfunction "PE2_37") (pintype "bidirectional"))
      (node (ref "U2") (pin "5") (pinfunction "TX_5") (pintype "bidirectional"))
    )
    (net (code "38") (name "/GPS_TXD") (class "Default")
      (node (ref "IC3") (pin "38") (pinfunction "PE3_38") (pintype "bidirectional"))
      (node (ref "U2") (pin "6") (pinfunction "RX_6") (pintype "bidirectional"))
    )
    (net (code "39") (name "/LED_STATUS") (class "Default")
      (node (ref "IC3") (pin "20") (pinfunction "PC5_20") (pintype "bidirectional"))
      (node (ref "LED1") (pin "C") (pinfunction "C_C") (pintype "passive"))
    )
    (net (code "40") (name "/MOT1_5V") (class "Default")
      (node (ref "JP1") (pin "3") (pinfunction "3_3") (pintype "passive"))
      (node (ref "X8") (pin "2") (pinfunction "S_2") (pintype "passive"))
    )
    (net (code "41") (name "/MOT1_A") (class "Default")
      (node (ref "B1") (pin "P$1") (pinfunction "S_P$1") (pintype "passive"))
      (node (ref "X1") (pin "1") (pinfunction "S_1") (pintype "passive"))
    )
    (net (code "42") (name "/MOT1_B") (class "Default")
      (node (ref "B2") (pin "P$1") (pinfunction "S_P$1") (pintype "passive"))
      (node (ref "X1") (pin "2") (pinfunction "S_2") (pintype "passive"))
    )
    (net (code "43") (name "/MOT1_C") (class "Default")
      (node (ref "B3") (pin "P$1") (pinfunction "S_P$1") (pintype "passive"))
      (node (ref "X1") (pin "3") (pinfunction "S_3") (pintype "passive"))
    )
    (net (code "44") (name "/MOT1_SIG") (class "Default")
      (node (ref "IC3") (pin "46") (pinfunction "PF1_46") (pintype "bidirectional"))
      (node (ref "X8") (pin "1") (pinfunction "S_1") (pintype "passive"))
    )
    (net (code "45") (name "/MOT2_5V") (class "Default")
      (node (ref "JP1") (pin "1") (pinfunction "1_1") (pintype "passive"))
      (node (ref "X9") (pin "2") (pinfunction "S_2") (pintype "passive"))
    )
    (net (code "46") (name "/MOT2_A") (class "Default")
      (node (ref "B4") (pin "P$1") (pinfunction "S_P$1") (pintype "passive"))
      (node (ref "X2") (pin "1") (pinfunction "S_1") (pintype "passive"))
    )
    (net (code "47") (name "/MOT2_B") (class "Default")
      (node (ref "B5") (pin "P$1") (pinfunction "S_P$1") (pintype "passive"))
      (node (ref "X2") (pin "2") (pinfunction "S_2") (pintype "passive"))
    )
    (net (code "48") (name "/MOT2_C") (class "Default")
      (node (ref "B6") (pin "P$1") (pinfunction "S_P$1") (pintype "passive"))
      (node (ref "X2") (pin "3") (pinfunction "S_3") (pintype "passive"))
    )
    (net (code "49") (name "/MOT2_SIG") (class "Default")
      (node (ref "IC3") (pin "45") (pinfunction "PF0_45") (pintype "bidirectional"))
      (node (ref "X9") (pin "1") (pinfunction "S_1") (pintype "passive"))
    )
    (net (code "50") (name "/PWR_CTL") (class "Default")
      (node (ref "IC3") (pin "68") (pinfunction "PJ3_68") (pintype "bidirectional"))
      (node (ref "R5") (pin "1") (pinfunction "1_1") (pintype "passive"))
    )
    (net (code "51") (name "/PWR_CTL1") (class "Default")
      (node (ref "IC3") (pin "81") (pinfunction "PK6_81") (pintype "bidirectional"))
      (node (ref "IC4") (pin "3") (pinfunction "IN1_3") (pintype "input"))
      (node (ref "R12") (pin "1") (pinfunction "1_1") (pintype "passive"))
    )
    (net (code "52") (name "/PWR_CTL2") (class "Default")
      (node (ref "IC3") (pin "79") (pinfunction "PK4_79") (pintype "bidirectional"))
      (node (ref "IC4") (pin "5") (pinfunction "IN2_5") (pintype "input"))
      (node (ref "R13") (pin "1") (pinfunction "1_1") (pintype "passive"))
    )
    (net (code "53") (name "/PWR_CTL3") (class "Default")
      (node (ref "IC3") (pin "77") (pinfunction "PK2_77") (pintype "bidirectional"))
      (node (ref "IC4") (pin "7") (pinfunction "IN3_7") (pintype "input"))
      (node (ref "R14") (pin "1") (pinfunction "1_1") (pintype "passive"))
    )
    (net (code "54") (name "/PWR_CTL4") (class "Default")
      (node (ref "IC3") (pin "75") (pinfunction "PK0_75") (pintype "bidirectional"))
      (node (ref "IC4") (pin "9") (pinfunction "IN4_9") (pintype "input"))
      (node (ref "R15") (pin "1") (pinfunction "1_1") (pintype "passive"))
    )
    (net (code "55") (name "/PWR_SENSE") (class "Default")
      (node (ref "D1") (pin "3") (pinfunction "C_3") (pintype "passive"))
      (node (ref "IC3") (pin "67") (pinfunction "PJ2_67") (pintype "bidirectional"))
      (node (ref "R6") (pin "1") (pinfunction "1_1") (pintype "passive"))
    )
    (net (code "56") (name "/RX1_TTL") (class "Default")
      (node (ref "IC1") (pin "9") (pinfunction "R1OUT_9") (pintype "output"))
      (node (ref "IC3") (pin "17") (pinfunction "PC2_17") (pintype "bidirectional"))
      (node (ref "IC6") (pin "4") (pinfunction "Y_4") (pintype "passive"))
    )
    (net (code "57") (name "/RX2_TTL") (class "Default")
      (node (ref "IC10") (pin "4") (pinfunction "Y_4") (pintype "passive"))
      (node (ref "IC3") (pin "21") (pinfunction "PC6_21") (pintype "bidirectional"))
      (node (ref "IC7") (pin "9") (pinfunction "R1OUT_9") (pintype "output"))
    )
    (net (code "58") (name "/RX3_TTL") (class "Default")
      (node (ref "IC11") (pin "9") (pinfunction "R1OUT_9") (pintype "output"))
      (node (ref "IC14") (pin "4") (pinfunction "Y_4") (pintype "passive"))
      (node (ref "IC3") (pin "31") (pinfunction "PD6_31") (pintype "bidirectional"))
    )
    (net (code "59") (name "/RX4_TTL") (class "Default")
      (node (ref "IC15") (pin "9") (pinfunction "R1OUT_9") (pintype "output"))
      (node (ref "IC18") (pin "4") (pinfunction "Y_4") (pintype "passive"))
      (node (ref "IC3") (pin "27") (pinfunction "PD2_27") (pintype "bidirectional"))
    )
    (net (code "60") (name "/S1_5V") (class "Default")
      (node (ref "IC5") (pin "5") (pinfunction "VCC_5") (pintype "passive"))
      (node (ref "PTC9") (pin "2") (pinfunction "2_2") (pintype "passive"))
      (node (ref "X4") (pin "4") (pinfunction "S_4") (pintype "passive"))
    )
    (net (code "61") (name "/S1_12V") (class "Default")
      (node (ref "T6") (pin "3") (pinfunction "S_3") (pintype "passive"))
      (node (ref "X4") (pin "1") (pinfunction "S_1") (pintype "passive"))
    )
    (net (code "62") (name "/S1_GPIO_A") (class "Default")
      (node (ref "PTC1") (pin "2") (pinfunction "2_2") (pintype "passive"))
      (node (ref "X4") (pin "5") (pinfunction "S_5") (pintype "passive"))
    )
    (net (code "63") (name "/S1_GPIO_B") (class "Default")
      (node (ref "PTC2") (pin "2") (pinfunction "2_2") (pintype "passive"))
      (node (ref "X4") (pin "6") (pinfunction "S_6") (pintype "passive"))
    )
    (net (code "64") (name "/S1_RX") (class "Default")
      (node (ref "IC1") (pin "8") (pinfunction "R1IN_8") (pintype "input"))
      (node (ref "R16") (pin "2") (pinfunction "2_2") (pintype "passive"))
      (node (ref "X4") (pin "2") (pinfunction "S_2") (pintype "passive"))
    )
    (net (code "65") (name "/S1_RX_33V") (class "Default")
      (node (ref "D3") (pin "3") (pinfunction "C2_3") (pintype "passive"))
      (node (ref "IC6") (pin "1") (pinfunction "A_1") (pintype "input"))
      (node (ref "R16") (pin "1") (pinfunction "1_1") (pintype "passive"))
    )
    (net (code "66") (name "/S1_TX") (class "Default")
      (node (ref "IC1") (pin "13") (pinfunction "T1OUT_13") (pintype "output"))
      (node (ref "IC5") (pin "4") (pinfunction "Y_4") (pintype "passive"))
      (node (ref "X4") (pin "3") (pinfunction "S_3") (pintype "passive"))
    )
    (net (code "67") (name "/S2_5V") (class "Default")
      (node (ref "IC9") (pin "5") (pinfunction "VCC_5") (pintype "passive"))
      (node (ref "PTC10") (pin "2") (pinfunction "2_2") (pintype "passive"))
      (node (ref "X5") (pin "4") (pinfunction "S_4") (pintype "passive"))
    )
    (net (code "68") (name "/S2_12V") (class "Default")
      (node (ref "T7") (pin "3") (pinfunction "S_3") (pintype "passive"))
      (node (ref "X5") (pin "1") (pinfunction "S_1") (pintype "passive"))
    )
    (net (code "69") (name "/S2_GPIO_A") (class "Default")
      (node (ref "PTC3") (pin "2") (pinfunction "2_2") (pintype "passive"))
      (node (ref "X5") (pin "5") (pinfunction "S_5") (pintype "passive"))
    )
    (net (code "70") (name "/S2_GPIO_B") (class "Default")
      (node (ref "PTC4") (pin "2") (pinfunction "2_2") (pintype "passive"))
      (node (ref "X5") (pin "6") (pinfunction "S_6") (pintype "passive"))
    )
    (net (code "71") (name "/S2_RX") (class "Default")
      (node (ref "IC7") (pin "8") (pinfunction "R1IN_8") (pintype "input"))
      (node (ref "R17") (pin "2") (pinfunction "2_2") (pintype "passive"))
      (node (ref "X5") (pin "2") (pinfunction "S_2") (pintype "passive"))
    )
    (net (code "72") (name "/S2_RX_33V") (class "Default")
      (node (ref "D3") (pin "2") (pinfunction "C1_2") (pintype "passive"))
      (node (ref "IC10") (pin "1") (pinfunction "A_1") (pintype "input"))
      (node (ref "R17") (pin "1") (pinfunction "1_1") (pintype "passive"))
    )
    (net (code "73") (name "/S2_TX") (class "Default")
      (node (ref "IC7") (pin "13") (pinfunction "T1OUT_13") (pintype "output"))
      (node (ref "IC9") (pin "4") (pinfunction "Y_4") (pintype "passive"))
      (node (ref "X5") (pin "3") (pinfunction "S_3") (pintype "passive"))
    )
    (net (code "74") (name "/S3_5V") (class "Default")
      (node (ref "IC13") (pin "5") (pinfunction "VCC_5") (pintype "passive"))
      (node (ref "PTC11") (pin "2") (pinfunction "2_2") (pintype "passive"))
      (node (ref "X6") (pin "4") (pinfunction "S_4") (pintype "passive"))
    )
    (net (code "75") (name "/S3_12V") (class "Default")
      (node (ref "T8") (pin "3") (pinfunction "S_3") (pintype "passive"))
      (node (ref "X6") (pin "1") (pinfunction "S_1") (pintype "passive"))
    )
    (net (code "76") (name "/S3_GPIO_A") (class "Default")
      (node (ref "PTC5") (pin "2") (pinfunction "2_2") (pintype "passive"))
      (node (ref "X6") (pin "5") (pinfunction "S_5") (pintype "passive"))
    )
    (net (code "77") (name "/S3_GPIO_B") (class "Default")
      (node (ref "PTC6") (pin "2") (pinfunction "2_2") (pintype "passive"))
      (node (ref "X6") (pin "6") (pinfunction "S_6") (pintype "passive"))
    )
    (net (code "78") (name "/S3_RX") (class "Default")
      (node (ref "IC11") (pin "8") (pinfunction "R1IN_8") (pintype "input"))
      (node (ref "R18") (pin "2") (pinfunction "2_2") (pintype "passive"))
      (node (ref "X6") (pin "2") (pinfunction "S_2") (pintype "passive"))
    )
    (net (code "79") (name "/S3_RX_33V") (class "Default")
      (node (ref "D7") (pin "3") (pinfunction "C2_3") (pintype "passive"))
      (node (ref "IC14") (pin "1") (pinfunction "A_1") (pintype "input"))
      (node (ref "R18") (pin "1") (pinfunction "1_1") (pintype "passive"))
    )
    (net (code "80") (name "/S3_TX") (class "Default")
      (node (ref "IC11") (pin "13") (pinfunction "T1OUT_13") (pintype "output"))
      (node (ref "IC13") (pin "4") (pinfunction "Y_4") (pintype "passive"))
      (node (ref "X6") (pin "3") (pinfunction "S_3") (pintype "passive"))
    )
    (net (code "81") (name "/S4_5V") (class "Default")
      (node (ref "IC17") (pin "5") (pinfunction "VCC_5") (pintype "passive"))
      (node (ref "PTC12") (pin "2") (pinfunction "2_2") (pintype "passive"))
      (node (ref "X7") (pin "4") (pinfunction "S_4") (pintype "passive"))
    )
    (net (code "82") (name "/S4_12V") (class "Default")
      (node (ref "T9") (pin "3") (pinfunction "S_3") (pintype "passive"))
      (node (ref "X7") (pin "1") (pinfunction "S_1") (pintype "passive"))
    )
    (net (code "83") (name "/S4_GPIO_A") (class "Default")
      (node (ref "PTC7") (pin "2") (pinfunction "2_2") (pintype "passive"))
      (node (ref "X7") (pin "5") (pinfunction "S_5") (pintype "passive"))
    )
    (net (code "84") (name "/S4_GPIO_B") (class "Default")
      (node (ref "PTC8") (pin "2") (pinfunction "2_2") (pintype "passive"))
      (node (ref "X7") (pin "6") (pinfunction "S_6") (pintype "passive"))
    )
    (net (code "85") (name "/S4_RX") (class "Default")
      (node (ref "IC15") (pin "8") (pinfunction "R1IN_8") (pintype "input"))
      (node (ref "R19") (pin "2") (pinfunction "2_2") (pintype "passive"))
      (node (ref "X7") (pin "2") (pinfunction "S_2") (pintype "passive"))
    )
    (net (code "86") (name "/S4_RX_33V") (class "Default")
      (node (ref "D7") (pin "2") (pinfunction "C1_2") (pintype "passive"))
      (node (ref "IC18") (pin "1") (pinfunction "A_1") (pintype "input"))
      (node (ref "R19") (pin "1") (pinfunction "1_1") (pintype "passive"))
    )
    (net (code "87") (name "/S4_TX") (class "Default")
      (node (ref "IC15") (pin "13") (pinfunction "T1OUT_13") (pintype "output"))
      (node (ref "IC17") (pin "4") (pinfunction "Y_4") (pintype "passive"))
      (node (ref "X7") (pin "3") (pinfunction "S_3") (pintype "passive"))
    )
    (net (code "88") (name "/TX1_TTL") (class "Default")
      (node (ref "IC1") (pin "11") (pinfunction "T1IN_11") (pintype "input"))
      (node (ref "IC3") (pin "18") (pinfunction "PC3_18") (pintype "bidirectional"))
      (node (ref "IC5") (pin "1") (pinfunction "A_1") (pintype "input"))
    )
    (net (code "89") (name "/TX2_TTL") (class "Default")
      (node (ref "IC3") (pin "22") (pinfunction "PC7_22") (pintype "bidirectional"))
      (node (ref "IC7") (pin "11") (pinfunction "T1IN_11") (pintype "input"))
      (node (ref "IC9") (pin "1") (pinfunction "A_1") (pintype "input"))
    )
    (net (code "90") (name "/TX3_TTL") (class "Default")
      (node (ref "IC11") (pin "11") (pinfunction "T1IN_11") (pintype "input"))
      (node (ref "IC13") (pin "1") (pinfunction "A_1") (pintype "input"))
      (node (ref "IC3") (pin "32") (pinfunction "PD7_32") (pintype "bidirectional"))
    )
    (net (code "91") (name "/TX4_TTL") (class "Default")
      (node (ref "IC15") (pin "11") (pinfunction "T1IN_11") (pintype "input"))
      (node (ref "IC17") (pin "1") (pinfunction "A_1") (pintype "input"))
      (node (ref "IC3") (pin "28") (pinfunction "PD3_28") (pintype "bidirectional"))
    )
    (net (code "92") (name "/USER_BUTTON") (class "Default")
      (node (ref "IC3") (pin "55") (pinfunction "PH0_55") (pintype "bidirectional"))
      (node (ref "S2") (pin "1") (pinfunction "1_1") (pintype "passive"))
    )
    (net (code "93") (name "/~{CHRG_FAULT}") (class "Default")
      (node (ref "IC2") (pin "5") (pinfunction "~{FAULT}_5") (pintype "bidirectional"))
      (node (ref "IC3") (pin "65") (pinfunction "PJ0_65") (pintype "bidirectional"))
    )
    (net (code "94") (name "/~{CHRG}") (class "Default")
      (node (ref "IC2") (pin "4") (pinfunction "~{CHRG}_4") (pintype "bidirectional"))
      (node (ref "IC3") (pin "66") (pinfunction "PJ1_66") (pintype "bidirectional"))
    )
    (net (code "95") (name "/~{EN232_1}") (class "Default")
      (node (ref "IC1") (pin "1") (pinfunction "~{EN}_1") (pintype "input"))
      (node (ref "IC19") (pin "9") (pinfunction "I_9") (pintype "input"))
      (node (ref "IC3") (pin "69") (pinfunction "PJ4_69") (pintype "bidirectional"))
    )
    (net (code "96") (name "/~{EN232_2}") (class "Default")
      (node (ref "IC19") (pin "5") (pinfunction "I_5") (pintype "input"))
      (node (ref "IC3") (pin "70") (pinfunction "PJ5_70") (pintype "bidirectional"))
      (node (ref "IC7") (pin "1") (pinfunction "~{EN}_1") (pintype "input"))
    )
    (net (code "97") (name "/~{EN232_3}") (class "Default")
      (node (ref "IC11") (pin "1") (pinfunction "~{EN}_1") (pintype "input"))
      (node (ref "IC19") (pin "3") (pinfunction "I_3") (pintype "input"))
      (node (ref "IC3") (pin "71") (pinfunction "PJ6_71") (pintype "bidirectional"))
    )
    (net (code "98") (name "/~{EN232_4}") (class "Default")
      (node (ref "IC15") (pin "1") (pinfunction "~{EN}_1") (pintype "input"))
      (node (ref "IC19") (pin "1") (pinfunction "I_1") (pintype "input"))
      (node (ref "IC3") (pin "72") (pinfunction "PJ7_72") (pintype "bidirectional"))
    )
    (net (code "99") (name "GND") (class "Default")
      (node (ref "B8") (pin "P$1") (pinfunction "S_P$1") (pintype "passive"))
      (node (ref "C1") (pin "-") (pinfunction "-_-") (pintype "passive"))
      (node (ref "C10") (pin "2") (pinfunction "2_2") (pintype "passive"))
      (node (ref "C11") (pin "2") (pinfunction "2_2") (pintype "passive"))
      (node (ref "C12") (pin "2") (pinfunction "2_2") (pintype "passive"))
      (node (ref "C14") (pin "2") (pinfunction "2_2") (pintype "passive"))
      (node (ref "C15") (pin "2") (pinfunction "2_2") (pintype "passive"))
      (node (ref "C18") (pin "2") (pinfunction "2_2") (pintype "passive"))
      (node (ref "C19") (pin "1") (pinfunction "1_1") (pintype "passive"))
      (node (ref "C20") (pin "2") (pinfunction "2_2") (pintype "passive"))
      (node (ref "C21") (pin "2") (pinfunction "2_2") (pintype "passive"))
      (node (ref "C22") (pin "2") (pinfunction "2_2") (pintype "passive"))
      (node (ref "C25") (pin "2") (pinfunction "2_2") (pintype "passive"))
      (node (ref "C26") (pin "1") (pinfunction "1_1") (pintype "passive"))
      (node (ref "C27") (pin "2") (pinfunction "2_2") (pintype "passive"))
      (node (ref "C28") (pin "2") (pinfunction "2_2") (pintype "passive"))
      (node (ref "C29") (pin "-") (pinfunction "-_-") (pintype "passive"))
      (node (ref "C32") (pin "2") (pinfunction "2_2") (pintype "passive"))
      (node (ref "C33") (pin "1") (pinfunction "1_1") (pintype "passive"))
      (node (ref "C34") (pin "2") (pinfunction "2_2") (pintype "passive"))
      (node (ref "C37") (pin "2") (pinfunction "2_2") (pintype "passive"))
      (node (ref "C4") (pin "2") (pinfunction "2_2") (pintype "passive"))
      (node (ref "C41") (pin "2") (pinfunction "2_2") (pintype "passive"))
      (node (ref "C43") (pin "2") (pinfunction "2_2") (pintype "passive"))
      (node (ref "C44") (pin "2") (pinfunction "2_2") (pintype "passive"))
      (node (ref "C45") (pin "2") (pinfunction "2_2") (pintype "passive"))
      (node (ref "C46") (pin "2") (pinfunction "2_2") (pintype "passive"))
      (node (ref "C47") (pin "2") (pinfunction "2_2") (pintype "passive"))
      (node (ref "C48") (pin "2") (pinfunction "2_2") (pintype "passive"))
      (node (ref "C5") (pin "1") (pinfunction "1_1") (pintype "passive"))
      (node (ref "C6") (pin "2") (pinfunction "2_2") (pintype "passive"))
      (node (ref "C7") (pin "2") (pinfunction "2_2") (pintype "passive"))
      (node (ref "C8") (pin "-") (pinfunction "-_-") (pintype "passive"))
      (node (ref "C9") (pin "2") (pinfunction "2_2") (pintype "passive"))
      (node (ref "D1") (pin "1") (pinfunction "A_1") (pintype "passive"))
      (node (ref "D10") (pin "A") (pinfunction "A_A") (pintype "passive"))
      (node (ref "D2") (pin "1") (pinfunction "A_1") (pintype "passive"))
      (node (ref "D3") (pin "1") (pinfunction "A_1") (pintype "passive"))
      (node (ref "D4") (pin "1") (pinfunction "A_1") (pintype "passive"))
      (node (ref "D6") (pin "1") (pinfunction "A_1") (pintype "passive"))
      (node (ref "D7") (pin "1") (pinfunction "A_1") (pintype "passive"))
      (node (ref "D8") (pin "1") (pinfunction "A_1") (pintype "passive"))
      (node (ref "IC1") (pin "14") (pinfunction "GND_14") (pintype "power_in"))
      (node (ref "IC10") (pin "2") (pinfunction "GND_2") (pintype "power_in"))
      (node (ref "IC11") (pin "14") (pinfunction "GND_14") (pintype "power_in"))
      (node (ref "IC12") (pin "4") (pinfunction "GND_4") (pintype "power_in"))
      (node (ref "IC13") (pin "2") (pinfunction "GND_2") (pintype "power_in"))
      (node (ref "IC14") (pin "2") (pinfunction "GND_2") (pintype "power_in"))
      (node (ref "IC15") (pin "14") (pinfunction "GND_14") (pintype "power_in"))
      (node (ref "IC16") (pin "1") (pinfunction "GND_1") (pintype "passive"))
      (node (ref "IC17") (pin "2") (pinfunction "GND_2") (pintype "power_in"))
      (node (ref "IC18") (pin "2") (pinfunction "GND_2") (pintype "power_in"))
      (node (ref "IC19") (pin "11") (pinfunction "I_11") (pintype "input"))
      (node (ref "IC19") (pin "13") (pinfunction "I_13") (pintype "input"))
      (node (ref "IC19") (pin "7") (pinfunction "GND_7") (pintype "power_in"))
      (node (ref "IC2") (pin "13") (pinfunction "GND_13") (pintype "power_in"))
      (node (ref "IC3") (pin "13") (pinfunction "GND1_13") (pintype "power_in"))
      (node (ref "IC3") (pin "23") (pinfunction "GND2_23") (pintype "power_in"))
      (node (ref "IC3") (pin "3") (pinfunction "GND_3") (pintype "power_in"))
      (node (ref "IC3") (pin "33") (pinfunction "GND3_33") (pintype "power_in"))
      (node (ref "IC3") (pin "43") (pinfunction "GND4_43") (pintype "power_in"))
      (node (ref "IC3") (pin "53") (pinfunction "GND5_53") (pintype "power_in"))
      (node (ref "IC3") (pin "63") (pinfunction "GND6_63") (pintype "power_in"))
      (node (ref "IC3") (pin "73") (pinfunction "GND7_73") (pintype "power_in"))
      (node (ref "IC3") (pin "84") (pinfunction "GND8_84") (pintype "power_in"))
      (node (ref "IC3") (pin "93") (pinfunction "GND9_93") (pintype "power_in"))
      (node (ref "IC4") (pin "1") (pinfunction "GND_1") (pintype "input"))
      (node (ref "IC4") (pin "10") (pinfunction "GND1_10") (pintype "input"))
      (node (ref "IC5") (pin "2") (pinfunction "GND_2") (pintype "power_in"))
      (node (ref "IC6") (pin "2") (pinfunction "GND_2") (pintype "power_in"))
      (node (ref "IC7") (pin "14") (pinfunction "GND_14") (pintype "power_in"))
      (node (ref "IC8") (pin "4") (pinfunction "GND_4") (pintype "power_in"))
      (node (ref "IC9") (pin "2") (pinfunction "GND_2") (pintype "power_in"))
      (node (ref "ISP1") (pin "6") (pinfunction "6_6") (pintype "passive"))
      (node (ref "R23") (pin "1") (pinfunction "1_1") (pintype "passive"))
      (node (ref "R24") (pin "1") (pinfunction "1_1") (pintype "passive"))
      (node (ref "R25") (pin "1") (pinfunction "1_1") (pintype "passive"))
      (node (ref "R26") (pin "1") (pinfunction "1_1") (pintype "passive"))
      (node (ref "R27") (pin "1") (pinfunction "1_1") (pintype "passive"))
      (node (ref "R30") (pin "1") (pinfunction "1_1") (pintype "passive"))
      (node (ref "S1") (pin "2") (pinfunction "2_2") (pintype "passive"))
      (node (ref "S2") (pin "2") (pinfunction "2_2") (pintype "passive"))
      (node (ref "T1") (pin "1") (pinfunction "C_1") (pintype "passive"))
      (node (ref "U1") (pin "1") (pinfunction "GND_1") (pintype "bidirectional"))
      (node (ref "U1") (pin "12") (pinfunction "GND1_12") (pintype "bidirectional"))
      (node (ref "U1") (pin "25") (pinfunction "GND2_25") (pintype "bidirectional"))
      (node (ref "U1") (pin "27") (pinfunction "GND3_27") (pintype "bidirectional"))
      (node (ref "U1") (pin "28") (pinfunction "GND4_28") (pintype "bidirectional"))
      (node (ref "U1") (pin "29") (pinfunction "GND5_29") (pintype "bidirectional"))
      (node (ref "U2") (pin "4") (pinfunction "GND_4") (pintype "bidirectional"))
      (node (ref "X10") (pin "NEG") (pinfunction "S_NEG") (pintype "passive"))
      (node (ref "X11") (pin "1") (pinfunction "1_1") (pintype "passive"))
      (node (ref "X12") (pin "NEG") (pinfunction "S_NEG") (pintype "passive"))
      (node (ref "X13") (pin "1") (pinfunction "1_1") (pintype "passive"))
      (node (ref "X14") (pin "2") (pinfunction "S_2") (pintype "passive"))
      (node (ref "X15") (pin "NEG") (pinfunction "S_NEG") (pintype "passive"))
      (node (ref "X16") (pin "NEG") (pinfunction "S_NEG") (pintype "passive"))
      (node (ref "X17") (pin "4") (pinfunction "S_4") (pintype "passive"))
      (node (ref "X3") (pin "2") (pinfunction "S_2") (pintype "passive"))
      (node (ref "X4") (pin "7") (pinfunction "S_7") (pintype "passive"))
      (node (ref "X5") (pin "7") (pinfunction "S_7") (pintype "passive"))
      (node (ref "X6") (pin "7") (pinfunction "S_7") (pintype "passive"))
      (node (ref "X7") (pin "7") (pinfunction "S_7") (pintype "passive"))
      (node (ref "X8") (pin "3") (pinfunction "S_3") (pintype "passive"))
      (node (ref "X9") (pin "3") (pinfunction "S_3") (pintype "passive"))
    )
    (net (code "100") (name "Net-(IC1A-C1+)") (class "Default")
      (node (ref "C2") (pin "1") (pinfunction "1_1") (pintype "passive"))
      (node (ref "IC1") (pin "2") (pinfunction "C1+_2") (pintype "passive"))
    )
    (net (code "101") (name "Net-(IC1A-C1-)") (class "Default")
      (node (ref "C2") (pin "2") (pinfunction "2_2") (pintype "passive"))
      (node (ref "IC1") (pin "4") (pinfunction "C1-_4") (pintype "passive"))
    )
    (net (code "102") (name "Net-(IC1A-C2+)") (class "Default")
      (node (ref "C3") (pin "1") (pinfunction "1_1") (pintype "passive"))
      (node (ref "IC1") (pin "5") (pinfunction "C2+_5") (pintype "passive"))
    )
    (net (code "103") (name "Net-(IC1A-C2-)") (class "Default")
      (node (ref "C3") (pin "2") (pinfunction "2_2") (pintype "passive"))
      (node (ref "IC1") (pin "6") (pinfunction "C2-_6") (pintype "passive"))
    )
    (net (code "104") (name "Net-(IC1A-V+)") (class "Default")
      (node (ref "C4") (pin "1") (pinfunction "1_1") (pintype "passive"))
      (node (ref "IC1") (pin "3") (pinfunction "V+_3") (pintype "passive"))
    )
    (net (code "105") (name "Net-(IC1A-V-)") (class "Default")
      (node (ref "C5") (pin "2") (pinfunction "2_2") (pintype "passive"))
      (node (ref "IC1") (pin "7") (pinfunction "V-_7") (pintype "passive"))
    )
    (net (code "106") (name "Net-(IC2-BOOST)") (class "Default")
      (node (ref "C42") (pin "2") (pinfunction "2_2") (pintype "passive"))
      (node (ref "D9") (pin "C") (pinfunction "C_C") (pintype "passive"))
      (node (ref "IC2") (pin "11") (pinfunction "BOOST_11") (pintype "output"))
    )
    (net (code "107") (name "Net-(IC2-SW)") (class "Default")
      (node (ref "C42") (pin "1") (pinfunction "1_1") (pintype "passive"))
      (node (ref "D10") (pin "C") (pinfunction "C_C") (pintype "passive"))
      (node (ref "IC2") (pin "12") (pinfunction "SW_12") (pintype "input"))
      (node (ref "L1") (pin "1") (pinfunction "1_1") (pintype "passive"))
    )
    (net (code "108") (name "Net-(IC2-TIMER)") (class "Default")
      (node (ref "C41") (pin "1") (pinfunction "1_1") (pintype "passive"))
      (node (ref "IC2") (pin "6") (pinfunction "TIMER_6") (pintype "bidirectional"))
    )
    (net (code "109") (name "Net-(IC2-VFB)") (class "Default")
      (node (ref "IC2") (pin "7") (pinfunction "VFB_7") (pintype "bidirectional"))
      (node (ref "R22") (pin "1") (pinfunction "1_1") (pintype "passive"))
      (node (ref "R24") (pin "2") (pinfunction "2_2") (pintype "passive"))
    )
    (net (code "110") (name "Net-(IC2-VIN)") (class "Default")
      (node (ref "C29") (pin "+") (pinfunction "+_+") (pintype "passive"))
      (node (ref "C7") (pin "1") (pinfunction "1_1") (pintype "passive"))
      (node (ref "D12") (pin "C") (pinfunction "C_C") (pintype "passive"))
      (node (ref "IC2") (pin "1") (pinfunction "VIN_1") (pintype "power_in"))
      (node (ref "IC2") (pin "2") (pinfunction "VREG_2") (pintype "input"))
      (node (ref "IC2") (pin "3") (pinfunction "~{SHDN}_3") (pintype "bidirectional"))
    )
    (net (code "111") (name "Net-(IC3-PDI_DATA)") (class "Default")
      (node (ref "IC3") (pin "89") (pinfunction "PDI_DATA_89") (pintype "bidirectional"))
      (node (ref "ISP1") (pin "1") (pinfunction "1_1") (pintype "passive"))
    )
    (net (code "112") (name "Net-(IC3-~{RESET}{slash}PDI_CLK)") (class "Default")
      (node (ref "IC3") (pin "90") (pinfunction "~{RESET}/PDI_CLK_90") (pintype "input"))
      (node (ref "ISP1") (pin "5") (pinfunction "5_5") (pintype "passive"))
      (node (ref "R2") (pin "1") (pinfunction "1_1") (pintype "passive"))
    )
    (net (code "113") (name "Net-(IC4-DS1)") (class "Default")
      (node (ref "IC4") (pin "19") (pinfunction "DS1_19") (pintype "output"))
      (node (ref "R8") (pin "1") (pinfunction "1_1") (pintype "passive"))
      (node (ref "T6") (pin "1") (pinfunction "D_1") (pintype "passive"))
      (node (ref "T6") (pin "2") (pinfunction "D1_2") (pintype "passive"))
      (node (ref "T6") (pin "5") (pinfunction "D2_5") (pintype "passive"))
      (node (ref "T6") (pin "6") (pinfunction "D3_6") (pintype "passive"))
    )
    (net (code "114") (name "Net-(IC4-DS2)") (class "Default")
      (node (ref "IC4") (pin "17") (pinfunction "DS2_17") (pintype "input"))
      (node (ref "R9") (pin "1") (pinfunction "1_1") (pintype "passive"))
      (node (ref "T7") (pin "1") (pinfunction "D_1") (pintype "passive"))
      (node (ref "T7") (pin "2") (pinfunction "D1_2") (pintype "passive"))
      (node (ref "T7") (pin "5") (pinfunction "D2_5") (pintype "passive"))
      (node (ref "T7") (pin "6") (pinfunction "D3_6") (pintype "passive"))
    )
    (net (code "115") (name "Net-(IC4-DS3)") (class "Default")
      (node (ref "IC4") (pin "15") (pinfunction "DS3_15") (pintype "output"))
      (node (ref "R10") (pin "1") (pinfunction "1_1") (pintype "passive"))
      (node (ref "T8") (pin "1") (pinfunction "D_1") (pintype "passive"))
      (node (ref "T8") (pin "2") (pinfunction "D1_2") (pintype "passive"))
      (node (ref "T8") (pin "5") (pinfunction "D2_5") (pintype "passive"))
      (node (ref "T8") (pin "6") (pinfunction "D3_6") (pintype "passive"))
    )
    (net (code "116") (name "Net-(IC4-DS4)") (class "Default")
      (node (ref "IC4") (pin "13") (pinfunction "DS4_13") (pintype "output"))
      (node (ref "R11") (pin "1") (pinfunction "1_1") (pintype "passive"))
      (node (ref "T9") (pin "1") (pinfunction "D_1") (pintype "passive"))
      (node (ref "T9") (pin "2") (pinfunction "D1_2") (pintype "passive"))
      (node (ref "T9") (pin "5") (pinfunction "D2_5") (pintype "passive"))
      (node (ref "T9") (pin "6") (pinfunction "D3_6") (pintype "passive"))
    )
    (net (code "117") (name "Net-(IC4-G1)") (class "Default")
      (node (ref "IC4") (pin "18") (pinfunction "G1_18") (pintype "output"))
      (node (ref "T6") (pin "4") (pinfunction "G_4") (pintype "passive"))
    )
    (net (code "118") (name "Net-(IC4-G2)") (class "Default")
      (node (ref "IC4") (pin "16") (pinfunction "G2_16") (pintype "output"))
      (node (ref "T7") (pin "4") (pinfunction "G_4") (pintype "passive"))
    )
    (net (code "119") (name "Net-(IC4-G3)") (class "Default")
      (node (ref "IC4") (pin "14") (pinfunction "G3_14") (pintype "input"))
      (node (ref "T8") (pin "4") (pinfunction "G_4") (pintype "passive"))
    )
    (net (code "120") (name "Net-(IC4-G4)") (class "Default")
      (node (ref "IC4") (pin "12") (pinfunction "G4_12") (pintype "output"))
      (node (ref "T9") (pin "4") (pinfunction "G_4") (pintype "passive"))
    )
    (net (code "121") (name "Net-(IC7A-C1+)") (class "Default")
      (node (ref "C16") (pin "1") (pinfunction "1_1") (pintype "passive"))
      (node (ref "IC7") (pin "2") (pinfunction "C1+_2") (pintype "passive"))
    )
    (net (code "122") (name "Net-(IC7A-C1-)") (class "Default")
      (node (ref "C16") (pin "2") (pinfunction "2_2") (pintype "passive"))
      (node (ref "IC7") (pin "4") (pinfunction "C1-_4") (pintype "passive"))
    )
    (net (code "123") (name "Net-(IC7A-C2+)") (class "Default")
      (node (ref "C17") (pin "1") (pinfunction "1_1") (pintype "passive"))
      (node (ref "IC7") (pin "5") (pinfunction "C2+_5") (pintype "passive"))
    )
    (net (code "124") (name "Net-(IC7A-C2-)") (class "Default")
      (node (ref "C17") (pin "2") (pinfunction "2_2") (pintype "passive"))
      (node (ref "IC7") (pin "6") (pinfunction "C2-_6") (pintype "passive"))
    )
    (net (code "125") (name "Net-(IC7A-V+)") (class "Default")
      (node (ref "C18") (pin "1") (pinfunction "1_1") (pintype "passive"))
      (node (ref "IC7") (pin "3") (pinfunction "V+_3") (pintype "passive"))
    )
    (net (code "126") (name "Net-(IC7A-V-)") (class "Default")
      (node (ref "C19") (pin "2") (pinfunction "2_2") (pintype "passive"))
      (node (ref "IC7") (pin "7") (pinfunction "V-_7") (pintype "passive"))
    )
    (net (code "127") (name "Net-(IC8-R_OS)") (class "Default")
      (node (ref "IC8") (pin "5") (pinfunction "R_OS_5") (pintype "input"))
      (node (ref "R26") (pin "2") (pinfunction "2_2") (pintype "passive"))
    )
    (net (code "128") (name "Net-(IC11A-C1+)") (class "Default")
      (node (ref "C23") (pin "1") (pinfunction "1_1") (pintype "passive"))
      (node (ref "IC11") (pin "2") (pinfunction "C1+_2") (pintype "passive"))
    )
    (net (code "129") (name "Net-(IC11A-C1-)") (class "Default")
      (node (ref "C23") (pin "2") (pinfunction "2_2") (pintype "passive"))
      (node (ref "IC11") (pin "4") (pinfunction "C1-_4") (pintype "passive"))
    )
    (net (code "130") (name "Net-(IC11A-C2+)") (class "Default")
      (node (ref "C24") (pin "1") (pinfunction "1_1") (pintype "passive"))
      (node (ref "IC11") (pin "5") (pinfunction "C2+_5") (pintype "passive"))
    )
    (net (code "131") (name "Net-(IC11A-C2-)") (class "Default")
      (node (ref "C24") (pin "2") (pinfunction "2_2") (pintype "passive"))
      (node (ref "IC11") (pin "6") (pinfunction "C2-_6") (pintype "passive"))
    )
    (net (code "132") (name "Net-(IC11A-V+)") (class "Default")
      (node (ref "C25") (pin "1") (pinfunction "1_1") (pintype "passive"))
      (node (ref "IC11") (pin "3") (pinfunction "V+_3") (pintype "passive"))
    )
    (net (code "133") (name "Net-(IC11A-V-)") (class "Default")
      (node (ref "C26") (pin "2") (pinfunction "2_2") (pintype "passive"))
      (node (ref "IC11") (pin "7") (pinfunction "V-_7") (pintype "passive"))
    )
    (net (code "134") (name "Net-(IC12-R_OS)") (class "Default")
      (node (ref "IC12") (pin "5") (pinfunction "R_OS_5") (pintype "input"))
      (node (ref "R27") (pin "2") (pinfunction "2_2") (pintype "passive"))
    )
    (net (code "135") (name "Net-(IC15A-C1+)") (class "Default")
      (node (ref "C30") (pin "1") (pinfunction "1_1") (pintype "passive"))
      (node (ref "IC15") (pin "2") (pinfunction "C1+_2") (pintype "passive"))
    )
    (net (code "136") (name "Net-(IC15A-C1-)") (class "Default")
      (node (ref "C30") (pin "2") (pinfunction "2_2") (pintype "passive"))
      (node (ref "IC15") (pin "4") (pinfunction "C1-_4") (pintype "passive"))
    )
    (net (code "137") (name "Net-(IC15A-C2+)") (class "Default")
      (node (ref "C31") (pin "1") (pinfunction "1_1") (pintype "passive"))
      (node (ref "IC15") (pin "5") (pinfunction "C2+_5") (pintype "passive"))
    )
    (net (code "138") (name "Net-(IC15A-C2-)") (class "Default")
      (node (ref "C31") (pin "2") (pinfunction "2_2") (pintype "passive"))
      (node (ref "IC15") (pin "6") (pinfunction "C2-_6") (pintype "passive"))
    )
    (net (code "139") (name "Net-(IC15A-V+)") (class "Default")
      (node (ref "C32") (pin "1") (pinfunction "1_1") (pintype "passive"))
      (node (ref "IC15") (pin "3") (pinfunction "V+_3") (pintype "passive"))
    )
    (net (code "140") (name "Net-(IC15A-V-)") (class "Default")
      (node (ref "C33") (pin "2") (pinfunction "2_2") (pintype "passive"))
      (node (ref "IC15") (pin "7") (pinfunction "V-_7") (pintype "passive"))
    )
    (net (code "141") (name "Net-(LED1-PadA)") (class "Default")
      (node (ref "LED1") (pin "A") (pinfunction "A_A") (pintype "passive"))
      (node (ref "R3") (pin "1") (pinfunction "1_1") (pintype "passive"))
    )
    (net (code "142") (name "Net-(LED2-PadA)") (class "Default")
      (node (ref "LED2") (pin "A") (pinfunction "A_A") (pintype "passive"))
      (node (ref "R7") (pin "1") (pinfunction "1_1") (pintype "passive"))
    )
    (net (code "143") (name "Net-(LED3-PadA)") (class "Default")
      (node (ref "LED3") (pin "A") (pinfunction "A_A") (pintype "passive"))
      (node (ref "R28") (pin "1") (pinfunction "1_1") (pintype "passive"))
    )
    (net (code "144") (name "Net-(Q1-G)") (class "Default")
      (node (ref "C13") (pin "2") (pinfunction "2_2") (pintype "passive"))
      (node (ref "Q1") (pin "1") (pinfunction "G_1") (pintype "passive"))
      (node (ref "R4") (pin "1") (pinfunction "1_1") (pintype "passive"))
      (node (ref "R6") (pin "2") (pinfunction "2_2") (pintype "passive"))
      (node (ref "S1") (pin "1") (pinfunction "1_1") (pintype "passive"))
      (node (ref "T1") (pin "2") (pinfunction "E_2") (pintype "passive"))
    )
    (net (code "145") (name "Net-(T1-B)") (class "Default")
      (node (ref "R5") (pin "2") (pinfunction "2_2") (pintype "passive"))
      (node (ref "T1") (pin "3") (pinfunction "B_3") (pintype "passive"))
    )
    (net (code "146") (name "Net-(U1-PIO5)") (class "Default")
      (node (ref "LED2") (pin "C") (pinfunction "C_C") (pintype "passive"))
      (node (ref "U1") (pin "21") (pinfunction "PIO5_21") (pintype "bidirectional"))
    )
    (net (code "147") (name "Net-(U2-LED)") (class "Default")
      (node (ref "LED3") (pin "C") (pinfunction "C_C") (pintype "passive"))
      (node (ref "U2") (pin "1") (pinfunction "LED_1") (pintype "bidirectional"))
    )
    (net (code "148") (name "Net-(X13B-1)") (class "Default")
      (node (ref "R31") (pin "1") (pinfunction "1_1") (pintype "passive"))
      (node (ref "X13") (pin "2") (pinfunction "1_2") (pintype "passive"))
    )
    (net (code "149") (name "Net-(X13C-1)") (class "Default")
      (node (ref "R1") (pin "1") (pinfunction "1_1") (pintype "passive"))
      (node (ref "X13") (pin "3") (pinfunction "1_3") (pintype "passive"))
    )
    (net (code "150") (name "Net-(X17A-S)") (class "Default")
      (node (ref "X17") (pin "2") (pinfunction "S_2") (pintype "passive"))
      (node (ref "X17") (pin "3") (pinfunction "S_3") (pintype "passive"))
    )
    (net (code "151") (name "Net-(X17C-S)") (class "Default")
      (node (ref "C15") (pin "1") (pinfunction "1_1") (pintype "passive"))
      (node (ref "L4") (pin "1") (pinfunction "1_1") (pintype "passive"))
      (node (ref "X17") (pin "1") (pinfunction "S_1") (pintype "passive"))
    )
    (net (code "152") (name "V+") (class "Default")
      (node (ref "C13") (pin "1") (pinfunction "1_1") (pintype "passive"))
      (node (ref "IC12") (pin "1") (pinfunction "VIN-_1") (pintype "passive"))
      (node (ref "Q1") (pin "2") (pinfunction "S_2") (pintype "passive"))
      (node (ref "R21") (pin "2") (pinfunction "2_2") (pintype "passive"))
      (node (ref "R4") (pin "2") (pinfunction "2_2") (pintype "passive"))
    )
    (net (code "153") (name "unconnected-(IC1A-FORCEON-Pad12)") (class "Default")
      (node (ref "IC1") (pin "12") (pinfunction "FORCEON_12") (pintype "input"))
    )
    (net (code "154") (name "unconnected-(IC1A-~{INVALID}-Pad10)") (class "Default")
      (node (ref "IC1") (pin "10") (pinfunction "~{INVALID}_10") (pintype "input"))
    )
    (net (code "155") (name "unconnected-(IC3-PB0-Pad5)") (class "Default")
      (node (ref "IC3") (pin "5") (pinfunction "PB0_5") (pintype "bidirectional"))
    )
    (net (code "156") (name "unconnected-(IC3-PB1-Pad6)") (class "Default")
      (node (ref "IC3") (pin "6") (pinfunction "PB1_6") (pintype "bidirectional"))
    )
    (net (code "157") (name "unconnected-(IC3-PB2-Pad7)") (class "Default")
      (node (ref "IC3") (pin "7") (pinfunction "PB2_7") (pintype "bidirectional"))
    )
    (net (code "158") (name "unconnected-(IC3-PB3-Pad8)") (class "Default")
      (node (ref "IC3") (pin "8") (pinfunction "PB3_8") (pintype "bidirectional"))
    )
    (net (code "159") (name "unconnected-(IC3-PC0-Pad15)") (class "Default")
      (node (ref "IC3") (pin "15") (pinfunction "PC0_15") (pintype "bidirectional"))
    )
    (net (code "160") (name "unconnected-(IC3-PC1-Pad16)") (class "Default")
      (node (ref "IC3") (pin "16") (pinfunction "PC1_16") (pintype "bidirectional"))
    )
    (net (code "161") (name "unconnected-(IC3-PC4-Pad19)") (class "Default")
      (node (ref "IC3") (pin "19") (pinfunction "PC4_19") (pintype "bidirectional"))
    )
    (net (code "162") (name "unconnected-(IC3-PF2-Pad47)") (class "Default")
      (node (ref "IC3") (pin "47") (pinfunction "PF2_47") (pintype "bidirectional"))
    )
    (net (code "163") (name "unconnected-(IC3-PF3-Pad48)") (class "Default")
      (node (ref "IC3") (pin "48") (pinfunction "PF3_48") (pintype "bidirectional"))
    )
    (net (code "164") (name "unconnected-(IC3-PH1-Pad56)") (class "Default")
      (node (ref "IC3") (pin "56") (pinfunction "PH1_56") (pintype "bidirectional"))
    )
    (net (code "165") (name "unconnected-(IC3-PH2-Pad57)") (class "Default")
      (node (ref "IC3") (pin "57") (pinfunction "PH2_57") (pintype "bidirectional"))
    )
    (net (code "166") (name "unconnected-(IC3-PH3-Pad58)") (class "Default")
      (node (ref "IC3") (pin "58") (pinfunction "PH3_58") (pintype "bidirectional"))
    )
    (net (code "167") (name "unconnected-(IC3-PH4-Pad59)") (class "Default")
      (node (ref "IC3") (pin "59") (pinfunction "PH4_59") (pintype "bidirectional"))
    )
    (net (code "168") (name "unconnected-(IC3-PH5-Pad60)") (class "Default")
      (node (ref "IC3") (pin "60") (pinfunction "PH5_60") (pintype "bidirectional"))
    )
    (net (code "169") (name "unconnected-(IC3-PH6-Pad61)") (class "Default")
      (node (ref "IC3") (pin "61") (pinfunction "PH6_61") (pintype "bidirectional"))
    )
    (net (code "170") (name "unconnected-(IC3-PH7-Pad62)") (class "Default")
      (node (ref "IC3") (pin "62") (pinfunction "PH7_62") (pintype "bidirectional"))
    )
    (net (code "171") (name "unconnected-(IC3-PQ0-Pad85)") (class "Default")
      (node (ref "IC3") (pin "85") (pinfunction "PQ0_85") (pintype "bidirectional"))
    )
    (net (code "172") (name "unconnected-(IC3-PQ1-Pad86)") (class "Default")
      (node (ref "IC3") (pin "86") (pinfunction "PQ1_86") (pintype "bidirectional"))
    )
    (net (code "173") (name "unconnected-(IC3-PQ2-Pad87)") (class "Default")
      (node (ref "IC3") (pin "87") (pinfunction "PQ2_87") (pintype "bidirectional"))
    )
    (net (code "174") (name "unconnected-(IC3-PQ3-Pad88)") (class "Default")
      (node (ref "IC3") (pin "88") (pinfunction "PQ3_88") (pintype "bidirectional"))
    )
    (net (code "175") (name "unconnected-(IC3-PR0(XT2)-Pad91)") (class "Default")
      (node (ref "IC3") (pin "91") (pinfunction "PR0(XT2)_91") (pintype "bidirectional"))
    )
    (net (code "176") (name "unconnected-(IC3-PR1(XT1)-Pad92)") (class "Default")
      (node (ref "IC3") (pin "92") (pinfunction "PR1(XT1)_92") (pintype "bidirectional"))
    )
    (net (code "177") (name "unconnected-(IC7A-FORCEON-Pad12)") (class "Default")
      (node (ref "IC7") (pin "12") (pinfunction "FORCEON_12") (pintype "input"))
    )
    (net (code "178") (name "unconnected-(IC7A-~{INVALID}-Pad10)") (class "Default")
      (node (ref "IC7") (pin "10") (pinfunction "~{INVALID}_10") (pintype "input"))
    )
    (net (code "179") (name "unconnected-(IC8-NC-Pad7)") (class "Default")
      (node (ref "IC8") (pin "7") (pinfunction "NC_7") (pintype "passive"))
    )
    (net (code "180") (name "unconnected-(IC11A-FORCEON-Pad12)") (class "Default")
      (node (ref "IC11") (pin "12") (pinfunction "FORCEON_12") (pintype "input"))
    )
    (net (code "181") (name "unconnected-(IC11A-~{INVALID}-Pad10)") (class "Default")
      (node (ref "IC11") (pin "10") (pinfunction "~{INVALID}_10") (pintype "input"))
    )
    (net (code "182") (name "unconnected-(IC12-NC-Pad7)") (class "Default")
      (node (ref "IC12") (pin "7") (pinfunction "NC_7") (pintype "passive"))
    )
    (net (code "183") (name "unconnected-(IC15A-FORCEON-Pad12)") (class "Default")
      (node (ref "IC15") (pin "12") (pinfunction "FORCEON_12") (pintype "input"))
    )
    (net (code "184") (name "unconnected-(IC15A-~{INVALID}-Pad10)") (class "Default")
      (node (ref "IC15") (pin "10") (pinfunction "~{INVALID}_10") (pintype "input"))
    )
    (net (code "185") (name "unconnected-(IC19E-O-Pad10)") (class "Default")
      (node (ref "IC19") (pin "10") (pinfunction "O_10") (pintype "output"))
    )
    (net (code "186") (name "unconnected-(IC19F-O-Pad12)") (class "Default")
      (node (ref "IC19") (pin "12") (pinfunction "O_12") (pintype "output"))
    )
    (net (code "187") (name "unconnected-(U1-AIO1-Pad35)") (class "Default")
      (node (ref "U1") (pin "35") (pinfunction "AIO1_35") (pintype "bidirectional"))
    )
    (net (code "188") (name "unconnected-(U1-AIO2-Pad30)") (class "Default")
      (node (ref "U1") (pin "30") (pinfunction "AIO2_30") (pintype "bidirectional"))
    )
    (net (code "189") (name "unconnected-(U1-NC-Pad26)") (class "Default")
      (node (ref "U1") (pin "26") (pinfunction "NC_26") (pintype "bidirectional"))
    )
    (net (code "190") (name "unconnected-(U1-PCMCLK-Pad7)") (class "Default")
      (node (ref "U1") (pin "7") (pinfunction "PCMCLK_7") (pintype "bidirectional"))
    )
    (net (code "191") (name "unconnected-(U1-PCMIN-Pad9)") (class "Default")
      (node (ref "U1") (pin "9") (pinfunction "PCMIN_9") (pintype "bidirectional"))
    )
    (net (code "192") (name "unconnected-(U1-PCMOUT-Pad10)") (class "Default")
      (node (ref "U1") (pin "10") (pinfunction "PCMOUT_10") (pintype "bidirectional"))
    )
    (net (code "193") (name "unconnected-(U1-PCMSYNC-Pad8)") (class "Default")
      (node (ref "U1") (pin "8") (pinfunction "PCMSYNC_8") (pintype "bidirectional"))
    )
    (net (code "194") (name "unconnected-(U1-PIO3-Pad20)") (class "Default")
      (node (ref "U1") (pin "20") (pinfunction "PIO3_20") (pintype "bidirectional"))
    )
    (net (code "195") (name "unconnected-(U1-PIO4-Pad22)") (class "Default")
      (node (ref "U1") (pin "22") (pinfunction "PIO4_22") (pintype "bidirectional"))
    )
    (net (code "196") (name "unconnected-(U1-PIO6-Pad3)") (class "Default")
      (node (ref "U1") (pin "3") (pinfunction "PIO6_3") (pintype "bidirectional"))
    )
    (net (code "197") (name "unconnected-(U1-PIO7-Pad4)") (class "Default")
      (node (ref "U1") (pin "4") (pinfunction "PIO7_4") (pintype "bidirectional"))
    )
    (net (code "198") (name "unconnected-(U1-PIO8-Pad31)") (class "Default")
      (node (ref "U1") (pin "31") (pinfunction "PIO8_31") (pintype "bidirectional"))
    )
    (net (code "199") (name "unconnected-(U1-PIO9-Pad32)") (class "Default")
      (node (ref "U1") (pin "32") (pinfunction "PIO9_32") (pintype "bidirectional"))
    )
    (net (code "200") (name "unconnected-(U1-PIO10-Pad33)") (class "Default")
      (node (ref "U1") (pin "33") (pinfunction "PIO10_33") (pintype "bidirectional"))
    )
    (net (code "201") (name "unconnected-(U1-PIO11-Pad34)") (class "Default")
      (node (ref "U1") (pin "34") (pinfunction "PIO11_34") (pintype "bidirectional"))
    )
    (net (code "202") (name "unconnected-(U1-SPICLK-Pad6)") (class "Default")
      (node (ref "U1") (pin "6") (pinfunction "SPICLK_6") (pintype "bidirectional"))
    )
    (net (code "203") (name "unconnected-(U1-SPICSB-Pad23)") (class "Default")
      (node (ref "U1") (pin "23") (pinfunction "SPICSB_23") (pintype "bidirectional"))
    )
    (net (code "204") (name "unconnected-(U1-SPIMISO-Pad24)") (class "Default")
      (node (ref "U1") (pin "24") (pinfunction "SPIMISO_24") (pintype "bidirectional"))
    )
    (net (code "205") (name "unconnected-(U1-SPIMOSI-Pad2)") (class "Default")
      (node (ref "U1") (pin "2") (pinfunction "SPIMOSI_2") (pintype "bidirectional"))
    )
    (net (code "206") (name "unconnected-(U1-USBD+-Pad17)") (class "Default")
      (node (ref "U1") (pin "17") (pinfunction "USBD+_17") (pintype "bidirectional"))
    )
    (net (code "207") (name "unconnected-(U1-USBD--Pad18)") (class "Default")
      (node (ref "U1") (pin "18") (pinfunction "USBD-_18") (pintype "bidirectional"))
    )
    (net (code "208") (name "unconnected-(U2-VBAT-Pad2)") (class "Default")
      (node (ref "U2") (pin "2") (pinfunction "VBAT_2") (pintype "bidirectional"))
    )
  )
)
